# rings_v30.net
KiCad netlist of a schematic drawn in EAGLE
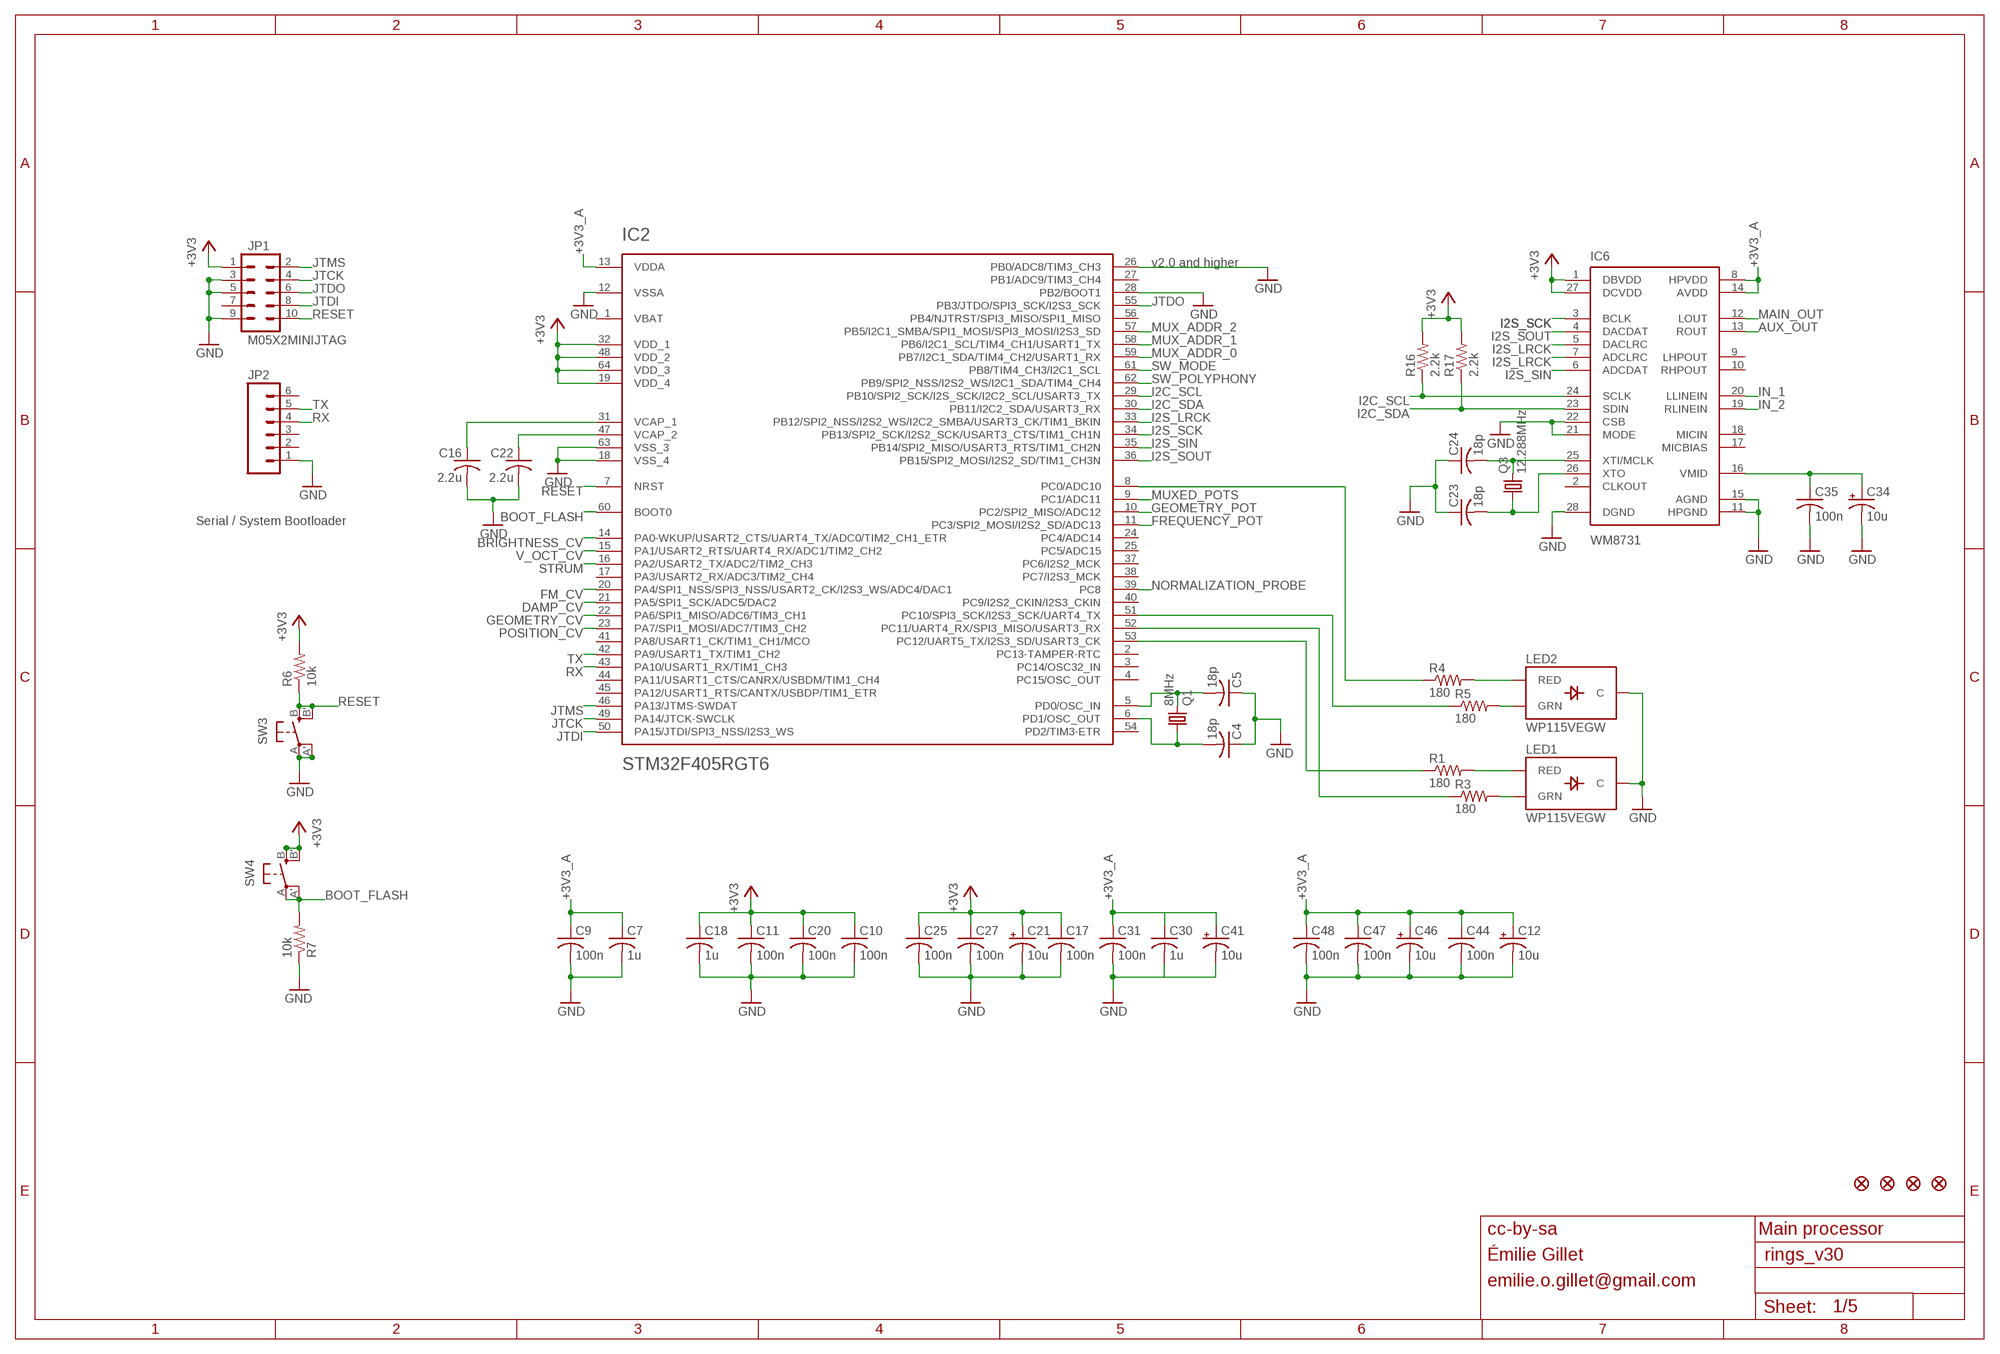
[diagram p0: schematic, sheet 1]
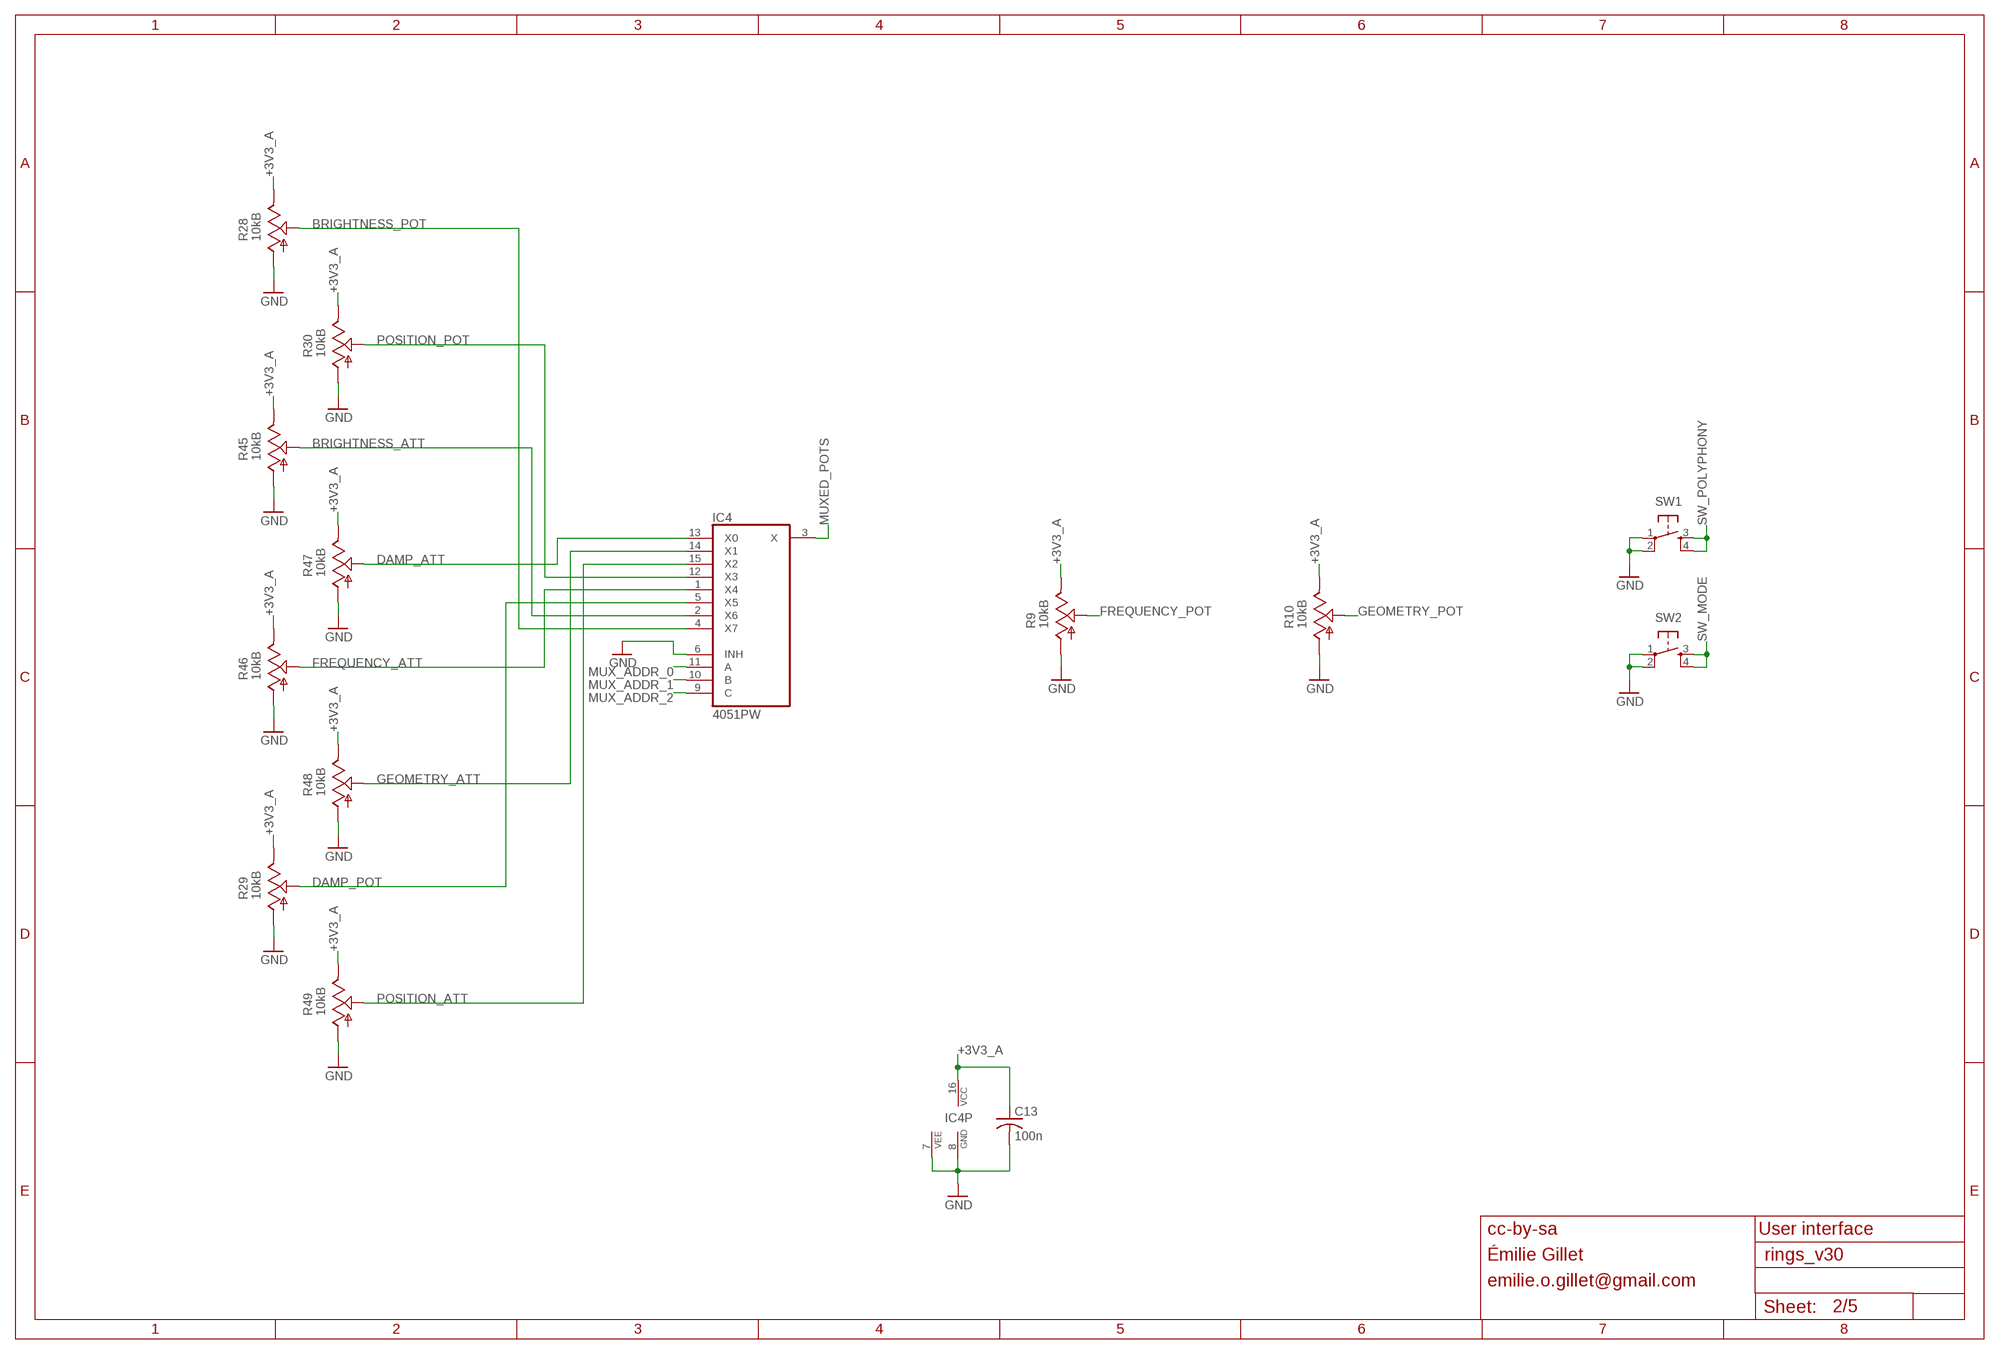
[diagram p1: schematic, sheet 2]
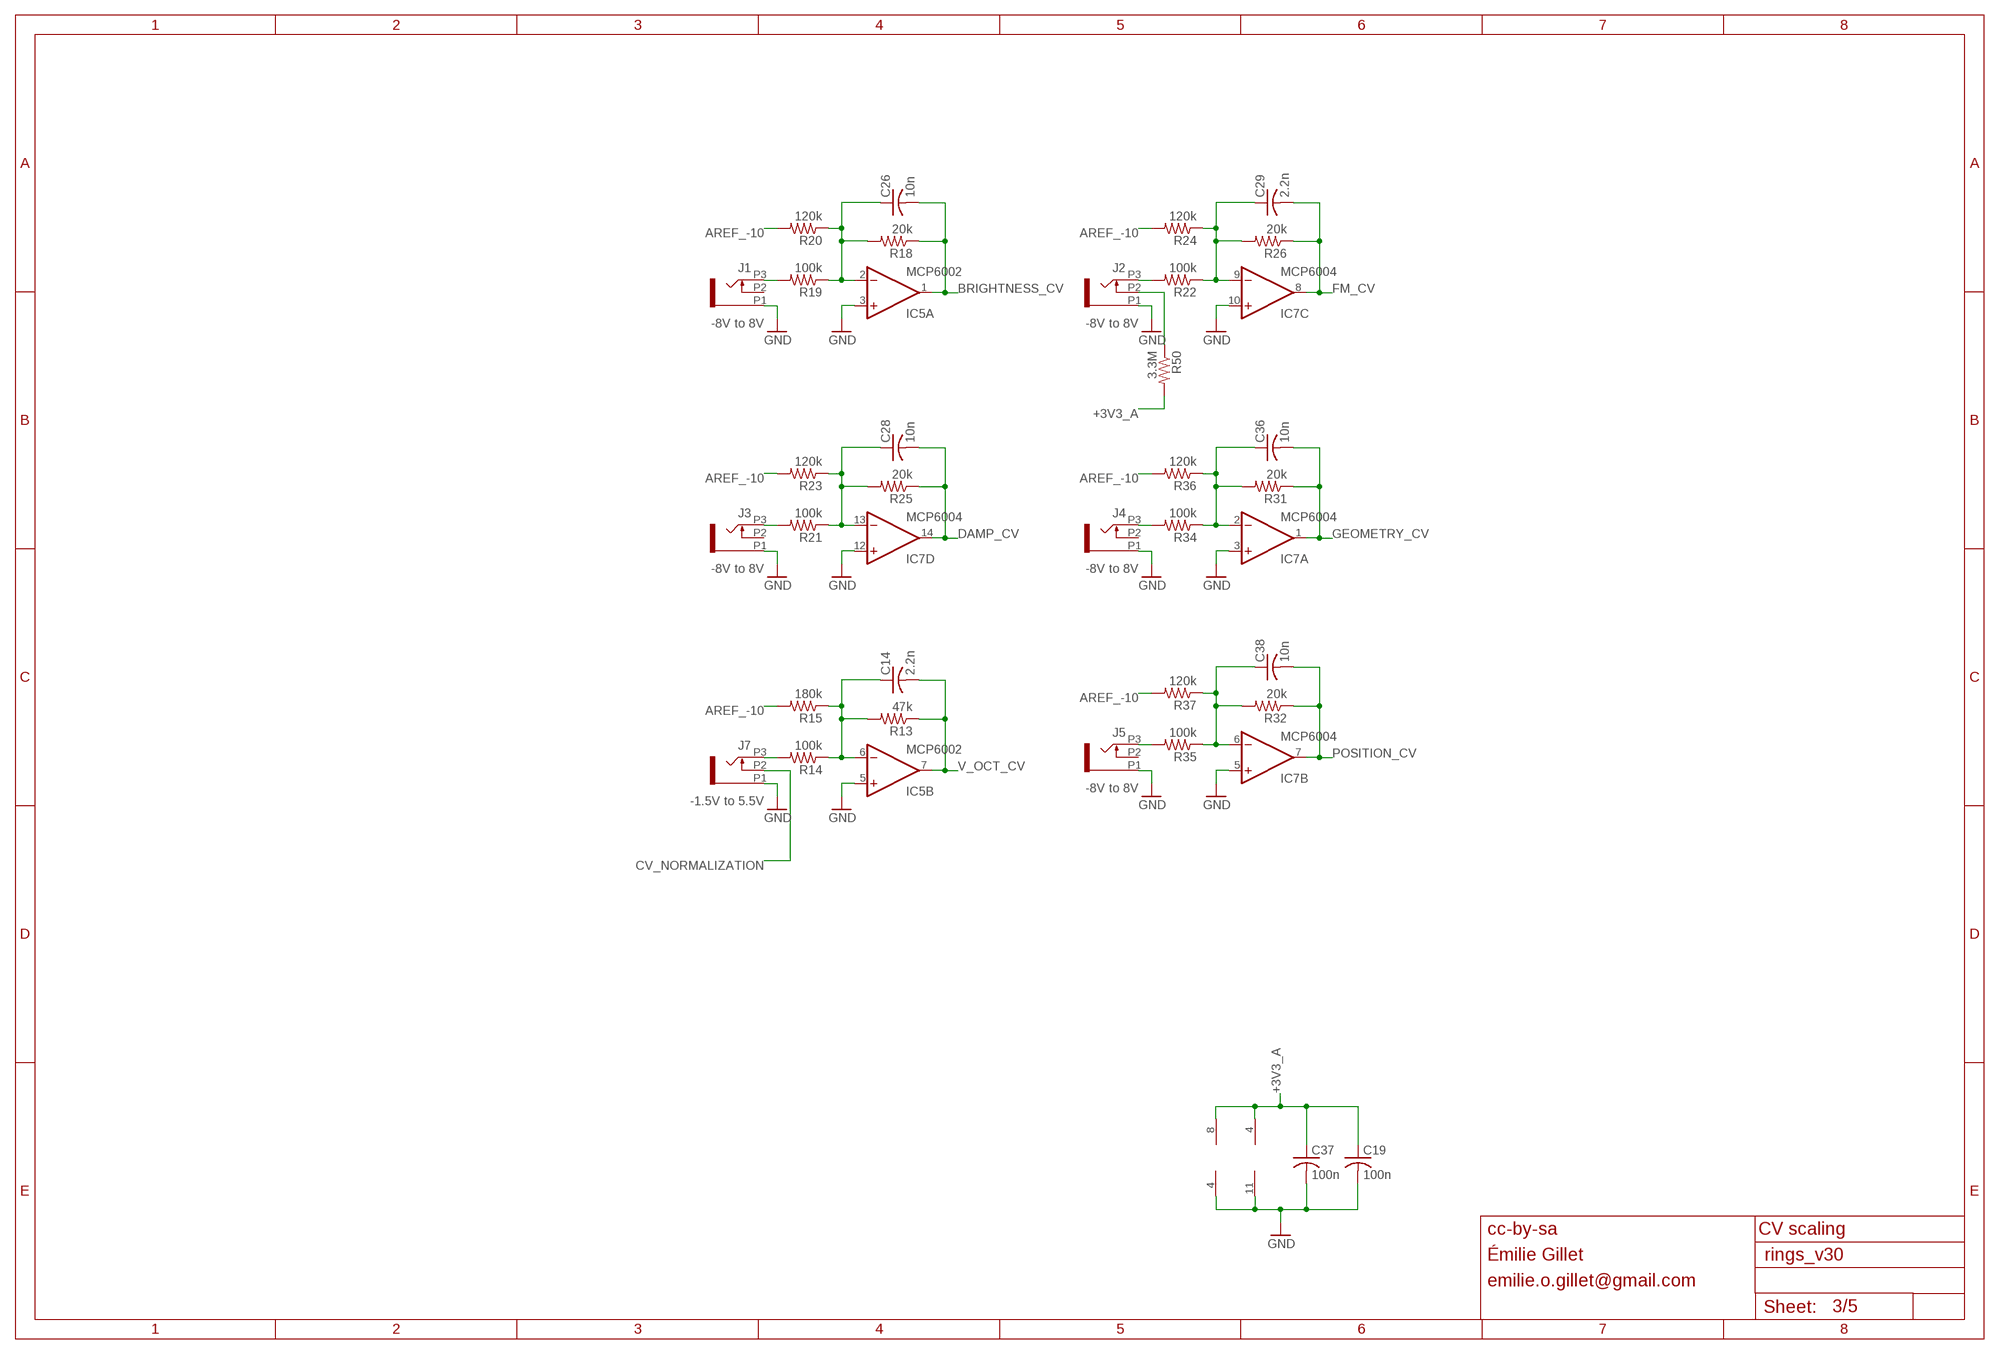
[diagram p2: schematic, sheet 3]
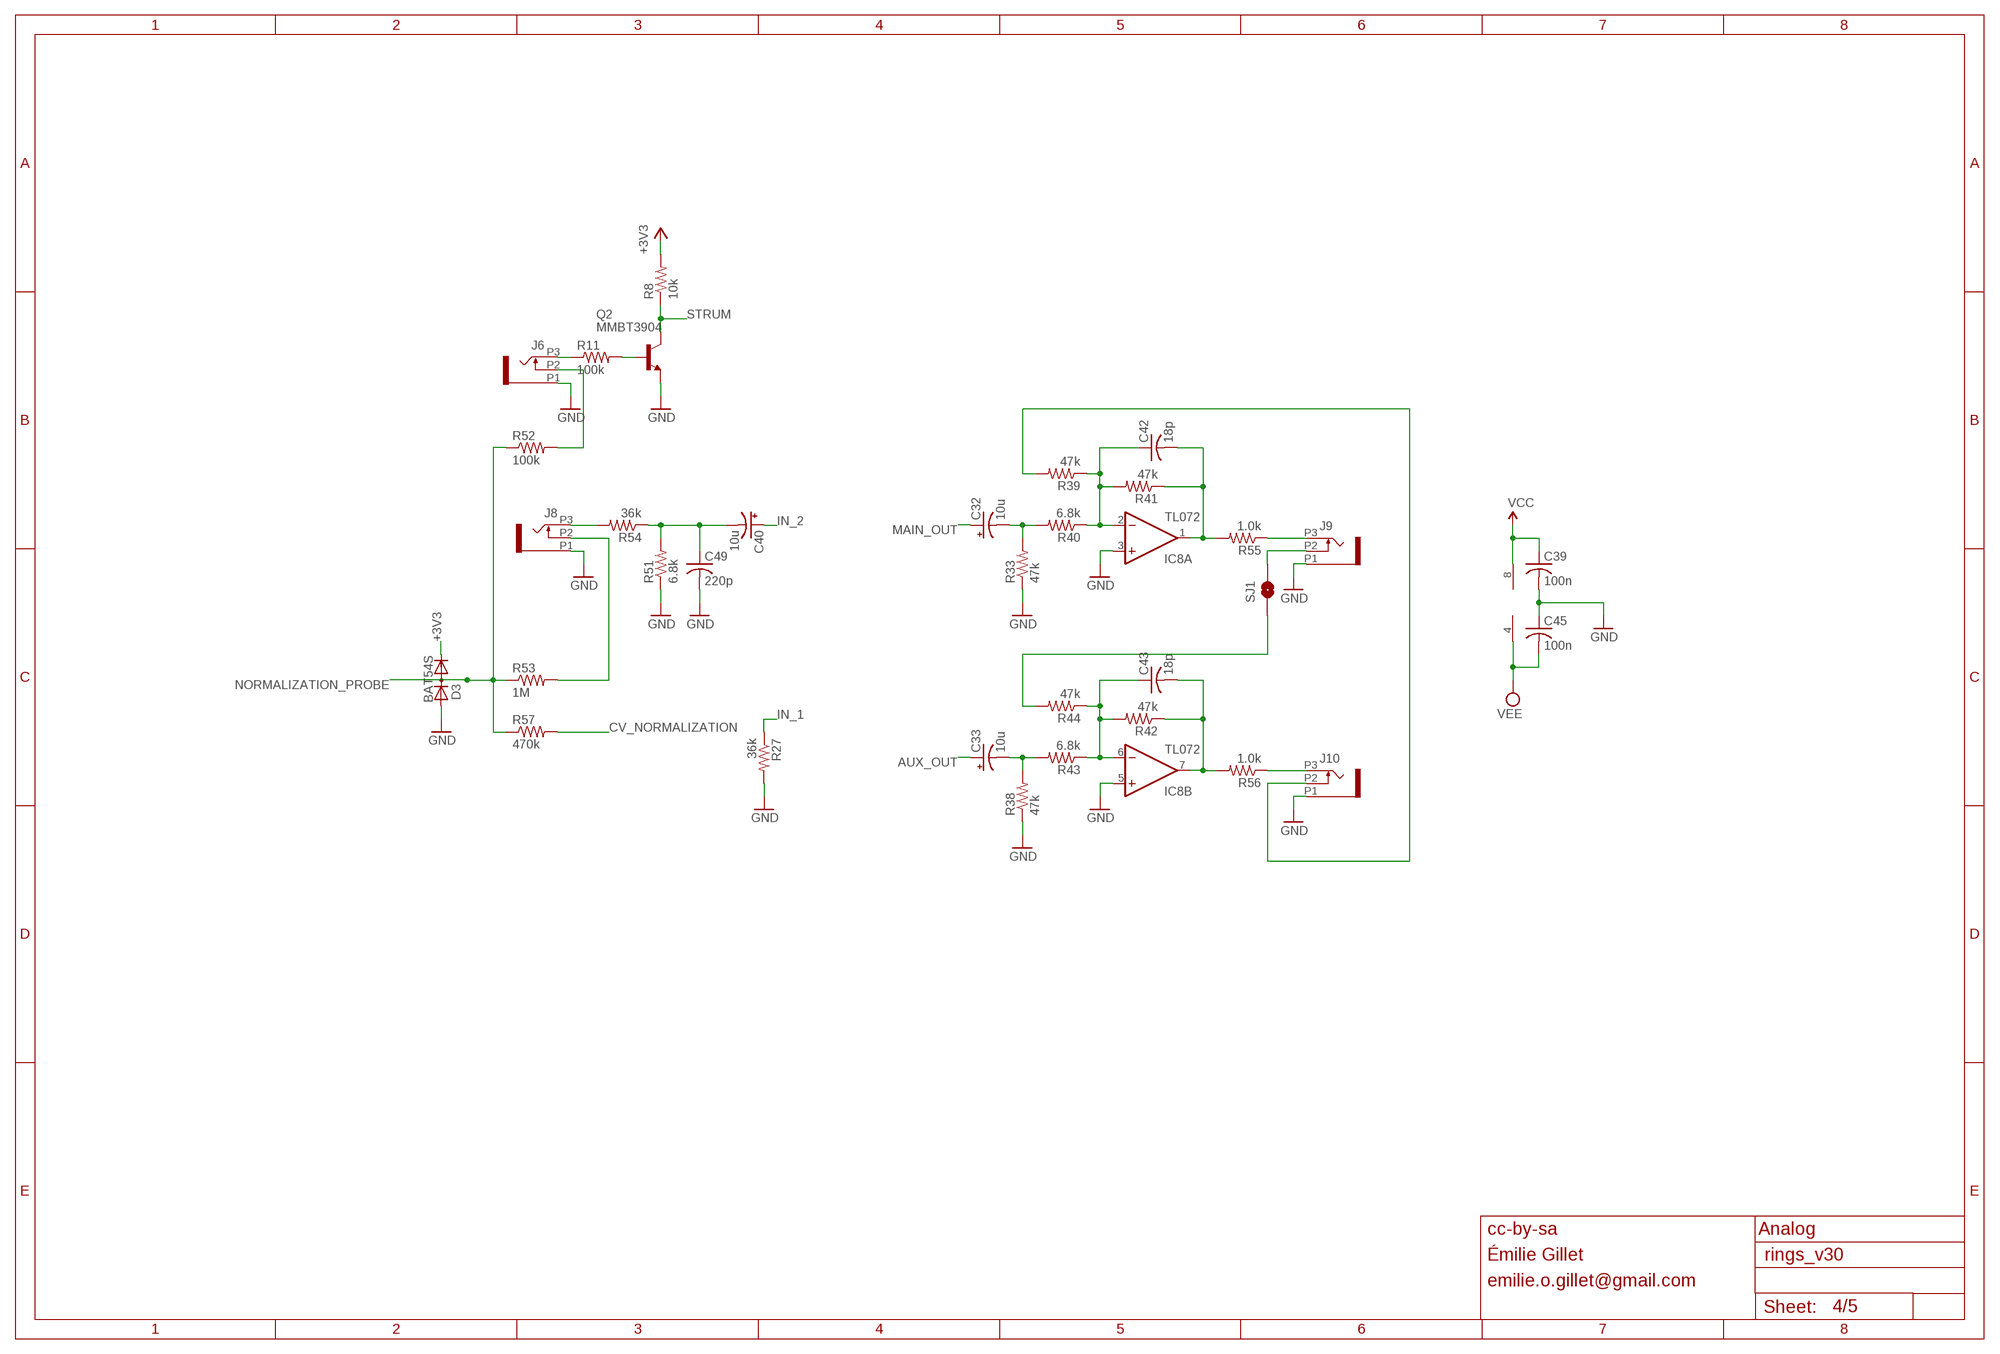
[diagram p3: schematic, sheet 4]
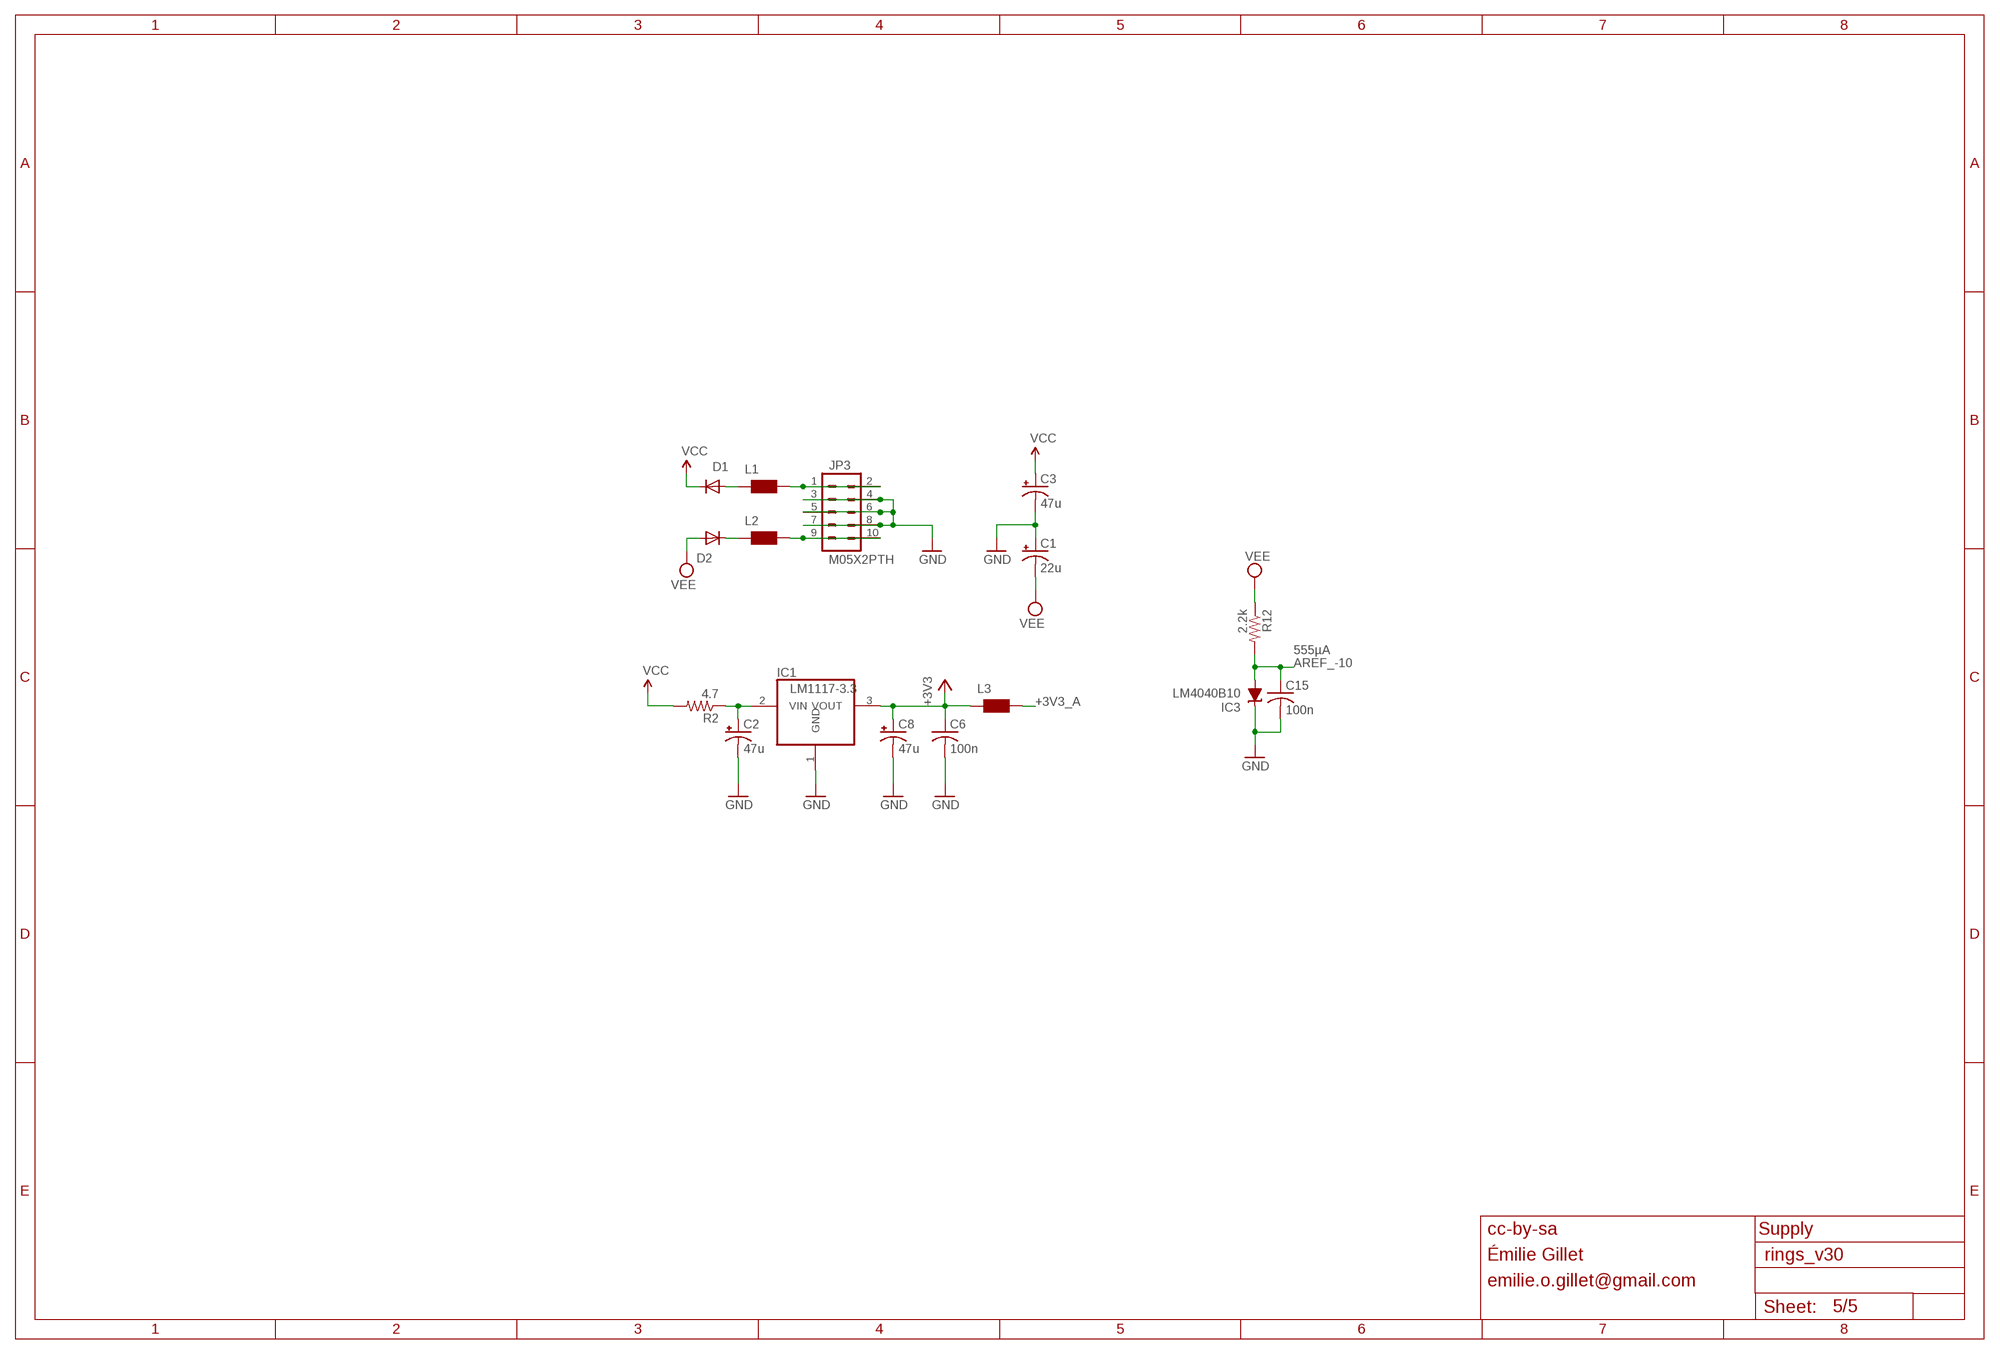
[diagram p4: schematic, sheet 5]

(export (version "E")
  (design (tool "Eeschema 10.0.6"))
  (components
    (comp (ref "C32")
      (value "10u")
      (footprint "eagle-import:PANASONIC_A")
      (libsource (lib "eagle-import") (part "CPOL-USA"))
    )
    (comp (ref "C33")
      (value "10u")
      (footprint "eagle-import:PANASONIC_A")
      (libsource (lib "eagle-import") (part "CPOL-USA"))
    )
    (comp (ref "C39")
      (value "100n")
      (footprint "eagle-import:C0603")
      (libsource (lib "eagle-import") (part "C-USC0603"))
    )
    (comp (ref "C40")
      (value "10u")
      (footprint "eagle-import:PANASONIC_A")
      (libsource (lib "eagle-import") (part "CPOL-USA"))
    )
    (comp (ref "C42")
      (value "18p")
      (footprint "eagle-import:C0603")
      (libsource (lib "eagle-import") (part "C-USC0603"))
    )
    (comp (ref "C43")
      (value "18p")
      (footprint "eagle-import:C0603")
      (libsource (lib "eagle-import") (part "C-USC0603"))
    )
    (comp (ref "C45")
      (value "100n")
      (footprint "eagle-import:C0603")
      (libsource (lib "eagle-import") (part "C-USC0603"))
    )
    (comp (ref "C49")
      (value "220p")
      (footprint "eagle-import:C0603")
      (libsource (lib "eagle-import") (part "C-USC0603"))
    )
    (comp (ref "D3")
      (value "BAT54S")
      (footprint "eagle-import:SOT23")
      (libsource (lib "eagle-import") (part "DIODE_2CACA-SOT23"))
    )
    (comp (ref "IC8")
      (value "TL072")
      (footprint "eagle-import:SO08")
      (libsource (lib "eagle-import") (part "og-linear_TL072D"))
    )
    (comp (ref "J6")
      (value "PJ301_THONKICONN6")
      (footprint "eagle-import:WQP_PJ_301M6")
      (libsource (lib "eagle-import") (part "PJ301_THONKICONN6"))
    )
    (comp (ref "J8")
      (value "PJ301_THONKICONN6")
      (footprint "eagle-import:WQP_PJ_301M6")
      (libsource (lib "eagle-import") (part "PJ301_THONKICONN6"))
    )
    (comp (ref "J9")
      (value "PJ301_THONKICONN6")
      (footprint "eagle-import:WQP_PJ_301M6")
      (libsource (lib "eagle-import") (part "PJ301_THONKICONN6"))
    )
    (comp (ref "J10")
      (value "PJ301_THONKICONN6")
      (footprint "eagle-import:WQP_PJ_301M6")
      (libsource (lib "eagle-import") (part "PJ301_THONKICONN6"))
    )
    (comp (ref "Q2")
      (value "MMBT3904")
      (footprint "eagle-import:SOT23-BEC")
      (libsource (lib "eagle-import") (part "-NPN-SOT23-BECMMBT3904LT1"))
    )
    (comp (ref "R8")
      (value "10k")
      (footprint "eagle-import:R0603")
      (libsource (lib "eagle-import") (part "R-US_R0603"))
    )
    (comp (ref "R11")
      (value "100k")
      (footprint "eagle-import:R0603")
      (libsource (lib "eagle-import") (part "R-US_R0603"))
    )
    (comp (ref "R27")
      (value "36k")
      (footprint "eagle-import:R0603")
      (libsource (lib "eagle-import") (part "R-US_R0603"))
    )
    (comp (ref "R33")
      (value "47k")
      (footprint "eagle-import:R0603")
      (libsource (lib "eagle-import") (part "R-US_R0603"))
    )
    (comp (ref "R38")
      (value "47k")
      (footprint "eagle-import:R0603")
      (libsource (lib "eagle-import") (part "R-US_R0603"))
    )
    (comp (ref "R39")
      (value "47k")
      (footprint "eagle-import:R0603")
      (libsource (lib "eagle-import") (part "R-US_R0603"))
    )
    (comp (ref "R40")
      (value "6.8k")
      (footprint "eagle-import:R0603")
      (libsource (lib "eagle-import") (part "R-US_R0603"))
    )
    (comp (ref "R41")
      (value "47k")
      (footprint "eagle-import:R0603")
      (libsource (lib "eagle-import") (part "R-US_R0603"))
    )
    (comp (ref "R42")
      (value "47k")
      (footprint "eagle-import:R0603")
      (libsource (lib "eagle-import") (part "R-US_R0603"))
    )
    (comp (ref "R43")
      (value "6.8k")
      (footprint "eagle-import:R0603")
      (libsource (lib "eagle-import") (part "R-US_R0603"))
    )
    (comp (ref "R44")
      (value "47k")
      (footprint "eagle-import:R0603")
      (libsource (lib "eagle-import") (part "R-US_R0603"))
    )
    (comp (ref "R51")
      (value "6.8k")
      (footprint "eagle-import:R0603")
      (libsource (lib "eagle-import") (part "R-US_R0603"))
    )
    (comp (ref "R52")
      (value "100k")
      (footprint "eagle-import:R0603")
      (libsource (lib "eagle-import") (part "R-US_R0603"))
    )
    (comp (ref "R53")
      (value "1M")
      (footprint "eagle-import:R0603")
      (libsource (lib "eagle-import") (part "R-US_R0603"))
    )
    (comp (ref "R54")
      (value "36k")
      (footprint "eagle-import:R0603")
      (libsource (lib "eagle-import") (part "R-US_R0603"))
    )
    (comp (ref "R55")
      (value "1.0k")
      (footprint "eagle-import:R0603")
      (libsource (lib "eagle-import") (part "R-US_R0603"))
    )
    (comp (ref "R56")
      (value "1.0k")
      (footprint "eagle-import:R0603")
      (libsource (lib "eagle-import") (part "R-US_R0603"))
    )
    (comp (ref "R57")
      (value "470k")
      (footprint "eagle-import:R0603")
      (libsource (lib "eagle-import") (part "R-US_R0603"))
    )
    (comp (ref "SJ1")
      (value "SOLDERJUMPERNC2")
      (footprint "eagle-import:SJ_2S-NOTRACE")
      (libsource (lib "eagle-import") (part "SOLDERJUMPERNC2"))
    )
    (comp (ref "C4")
      (value "18p")
      (footprint "eagle-import:C0603")
      (libsource (lib "eagle-import") (part "C-USC0603"))
    )
    (comp (ref "C5")
      (value "18p")
      (footprint "eagle-import:C0603")
      (libsource (lib "eagle-import") (part "C-USC0603"))
    )
    (comp (ref "C7")
      (value "1u")
      (footprint "eagle-import:C0603")
      (libsource (lib "eagle-import") (part "C-USC0603"))
    )
    (comp (ref "C9")
      (value "100n")
      (footprint "eagle-import:C0603")
      (libsource (lib "eagle-import") (part "C-USC0603"))
    )
    (comp (ref "C10")
      (value "100n")
      (footprint "eagle-import:C0603")
      (libsource (lib "eagle-import") (part "C-USC0603"))
    )
    (comp (ref "C11")
      (value "100n")
      (footprint "eagle-import:C0603")
      (libsource (lib "eagle-import") (part "C-USC0603"))
    )
    (comp (ref "C12")
      (value "10u")
      (footprint "eagle-import:PANASONIC_A")
      (libsource (lib "eagle-import") (part "CPOL-USA"))
    )
    (comp (ref "C16")
      (value "2.2u")
      (footprint "eagle-import:C0805")
      (libsource (lib "eagle-import") (part "C-USC0805"))
    )
    (comp (ref "C17")
      (value "100n")
      (footprint "eagle-import:C0603")
      (libsource (lib "eagle-import") (part "C-USC0603"))
    )
    (comp (ref "C18")
      (value "1u")
      (footprint "eagle-import:C0603")
      (libsource (lib "eagle-import") (part "C-USC0603"))
    )
    (comp (ref "C20")
      (value "100n")
      (footprint "eagle-import:C0603")
      (libsource (lib "eagle-import") (part "C-USC0603"))
    )
    (comp (ref "C21")
      (value "10u")
      (footprint "eagle-import:PANASONIC_A")
      (libsource (lib "eagle-import") (part "CPOL-USA"))
    )
    (comp (ref "C22")
      (value "2.2u")
      (footprint "eagle-import:C0805")
      (libsource (lib "eagle-import") (part "C-USC0805"))
    )
    (comp (ref "C23")
      (value "18p")
      (footprint "eagle-import:C0603")
      (libsource (lib "eagle-import") (part "C-USC0603"))
    )
    (comp (ref "C24")
      (value "18p")
      (footprint "eagle-import:C0603")
      (libsource (lib "eagle-import") (part "C-USC0603"))
    )
    (comp (ref "C25")
      (value "100n")
      (footprint "eagle-import:C0603")
      (libsource (lib "eagle-import") (part "C-USC0603"))
    )
    (comp (ref "C27")
      (value "100n")
      (footprint "eagle-import:C0603")
      (libsource (lib "eagle-import") (part "C-USC0603"))
    )
    (comp (ref "C30")
      (value "1u")
      (footprint "eagle-import:C0603")
      (libsource (lib "eagle-import") (part "C-USC0603"))
    )
    (comp (ref "C31")
      (value "100n")
      (footprint "eagle-import:C0603")
      (libsource (lib "eagle-import") (part "C-USC0603"))
    )
    (comp (ref "C34")
      (value "10u")
      (footprint "eagle-import:PANASONIC_A")
      (libsource (lib "eagle-import") (part "CPOL-USA"))
    )
    (comp (ref "C35")
      (value "100n")
      (footprint "eagle-import:C0603")
      (libsource (lib "eagle-import") (part "C-USC0603"))
    )
    (comp (ref "C41")
      (value "10u")
      (footprint "eagle-import:PANASONIC_A")
      (libsource (lib "eagle-import") (part "CPOL-USA"))
    )
    (comp (ref "C44")
      (value "100n")
      (footprint "eagle-import:C0603")
      (libsource (lib "eagle-import") (part "C-USC0603"))
    )
    (comp (ref "C46")
      (value "10u")
      (footprint "eagle-import:PANASONIC_A")
      (libsource (lib "eagle-import") (part "CPOL-USA"))
    )
    (comp (ref "C47")
      (value "100n")
      (footprint "eagle-import:C0603")
      (libsource (lib "eagle-import") (part "C-USC0603"))
    )
    (comp (ref "C48")
      (value "100n")
      (footprint "eagle-import:C0603")
      (libsource (lib "eagle-import") (part "C-USC0603"))
    )
    (comp (ref "F1")
      (value "FIDUCIAL1X2")
      (footprint "eagle-import:FIDUCIAL-1X2")
      (libsource (lib "eagle-import") (part "FIDUCIAL1X2"))
    )
    (comp (ref "F2")
      (value "FIDUCIAL1X2")
      (footprint "eagle-import:FIDUCIAL-1X2")
      (libsource (lib "eagle-import") (part "FIDUCIAL1X2"))
    )
    (comp (ref "F3")
      (value "FIDUCIAL1X2")
      (footprint "eagle-import:FIDUCIAL-1X2")
      (libsource (lib "eagle-import") (part "FIDUCIAL1X2"))
    )
    (comp (ref "F4")
      (value "FIDUCIAL1X2")
      (footprint "eagle-import:FIDUCIAL-1X2")
      (libsource (lib "eagle-import") (part "FIDUCIAL1X2"))
    )
    (comp (ref "IC2")
      (value "STM32F405RGT6")
      (footprint "eagle-import:TQFP-10X10-64")
      (libsource (lib "eagle-import") (part "STM32F20X"))
    )
    (comp (ref "IC6")
      (value "WM8731")
      (footprint "eagle-import:SSOP28")
      (libsource (lib "eagle-import") (part "WM8731"))
    )
    (comp (ref "JP1")
      (value "M05X2MINIJTAG")
      (footprint "eagle-import:2X5-1.27")
      (libsource (lib "eagle-import") (part "M05X2MINIJTAG"))
    )
    (comp (ref "JP2")
      (value "M06SIP")
      (footprint "eagle-import:1X06")
      (libsource (lib "eagle-import") (part "M06SIP"))
    )
    (comp (ref "LED1")
      (value "WP115VEGW")
      (footprint "eagle-import:LED-BICOLOR-THROUGHHOLE")
      (libsource (lib "eagle-import") (part "LED-BICOLOR-THROUGHHOLE"))
    )
    (comp (ref "LED2")
      (value "WP115VEGW")
      (footprint "eagle-import:LED-BICOLOR-THROUGHHOLE")
      (libsource (lib "eagle-import") (part "LED-BICOLOR-THROUGHHOLE"))
    )
    (comp (ref "Q1")
      (value "8MHz")
      (footprint "eagle-import:HC49UP")
      (libsource (lib "eagle-import") (part "CRYSTALHC49UP"))
    )
    (comp (ref "Q3")
      (value "12.288MHz")
      (footprint "eagle-import:HC49UP")
      (libsource (lib "eagle-import") (part "CRYSTALHC49UP"))
    )
    (comp (ref "R1")
      (value "180")
      (footprint "eagle-import:R0603")
      (libsource (lib "eagle-import") (part "R-US_R0603"))
    )
    (comp (ref "R3")
      (value "180")
      (footprint "eagle-import:R0603")
      (libsource (lib "eagle-import") (part "R-US_R0603"))
    )
    (comp (ref "R4")
      (value "180")
      (footprint "eagle-import:R0603")
      (libsource (lib "eagle-import") (part "R-US_R0603"))
    )
    (comp (ref "R5")
      (value "180")
      (footprint "eagle-import:R0603")
      (libsource (lib "eagle-import") (part "R-US_R0603"))
    )
    (comp (ref "R6")
      (value "10k")
      (footprint "eagle-import:R0603")
      (libsource (lib "eagle-import") (part "R-US_R0603"))
    )
    (comp (ref "R7")
      (value "10k")
      (footprint "eagle-import:R0603")
      (libsource (lib "eagle-import") (part "R-US_R0603"))
    )
    (comp (ref "R16")
      (value "2.2k")
      (footprint "eagle-import:R0603")
      (libsource (lib "eagle-import") (part "R-US_R0603"))
    )
    (comp (ref "R17")
      (value "2.2k")
      (footprint "eagle-import:R0603")
      (libsource (lib "eagle-import") (part "R-US_R0603"))
    )
    (comp (ref "SW3")
      (value "EVQQ2")
      (footprint "eagle-import:EVQ-Q2")
      (libsource (lib "eagle-import") (part "EVQQ2"))
    )
    (comp (ref "SW4")
      (value "EVQQ2")
      (footprint "eagle-import:EVQ-Q2")
      (libsource (lib "eagle-import") (part "EVQQ2"))
    )
    (comp (ref "C14")
      (value "2.2n")
      (footprint "eagle-import:C0603")
      (libsource (lib "eagle-import") (part "C-USC0603"))
    )
    (comp (ref "C19")
      (value "100n")
      (footprint "eagle-import:C0603")
      (libsource (lib "eagle-import") (part "C-USC0603"))
    )
    (comp (ref "C26")
      (value "10n")
      (footprint "eagle-import:C0603")
      (libsource (lib "eagle-import") (part "C-USC0603"))
    )
    (comp (ref "C28")
      (value "10n")
      (footprint "eagle-import:C0603")
      (libsource (lib "eagle-import") (part "C-USC0603"))
    )
    (comp (ref "C29")
      (value "2.2n")
      (footprint "eagle-import:C0603")
      (libsource (lib "eagle-import") (part "C-USC0603"))
    )
    (comp (ref "C36")
      (value "10n")
      (footprint "eagle-import:C0603")
      (libsource (lib "eagle-import") (part "C-USC0603"))
    )
    (comp (ref "C37")
      (value "100n")
      (footprint "eagle-import:C0603")
      (libsource (lib "eagle-import") (part "C-USC0603"))
    )
    (comp (ref "C38")
      (value "10n")
      (footprint "eagle-import:C0603")
      (libsource (lib "eagle-import") (part "C-USC0603"))
    )
    (comp (ref "IC5")
      (value "MCP6002")
      (footprint "eagle-import:SO08")
      (libsource (lib "eagle-import") (part "TL072D"))
    )
    (comp (ref "IC7")
      (value "MCP6004")
      (footprint "eagle-import:SO14")
      (libsource (lib "eagle-import") (part "TL074D"))
    )
    (comp (ref "J1")
      (value "PJ301_THONKICONN6")
      (footprint "eagle-import:WQP_PJ_301M6")
      (libsource (lib "eagle-import") (part "PJ301_THONKICONN6"))
    )
    (comp (ref "J2")
      (value "PJ301_THONKICONN6")
      (footprint "eagle-import:WQP_PJ_301M6")
      (libsource (lib "eagle-import") (part "PJ301_THONKICONN6"))
    )
    (comp (ref "J3")
      (value "PJ301_THONKICONN6")
      (footprint "eagle-import:WQP_PJ_301M6")
      (libsource (lib "eagle-import") (part "PJ301_THONKICONN6"))
    )
    (comp (ref "J4")
      (value "PJ301_THONKICONN6")
      (footprint "eagle-import:WQP_PJ_301M6")
      (libsource (lib "eagle-import") (part "PJ301_THONKICONN6"))
    )
    (comp (ref "J5")
      (value "PJ301_THONKICONN6")
      (footprint "eagle-import:WQP_PJ_301M6")
      (libsource (lib "eagle-import") (part "PJ301_THONKICONN6"))
    )
    (comp (ref "J7")
      (value "PJ301_THONKICONN6")
      (footprint "eagle-import:WQP_PJ_301M6")
      (libsource (lib "eagle-import") (part "PJ301_THONKICONN6"))
    )
    (comp (ref "R13")
      (value "47k")
      (footprint "eagle-import:R0603")
      (libsource (lib "eagle-import") (part "R-US_R0603"))
    )
    (comp (ref "R14")
      (value "100k")
      (footprint "eagle-import:R0603")
      (libsource (lib "eagle-import") (part "R-US_R0603"))
    )
    (comp (ref "R15")
      (value "180k")
      (footprint "eagle-import:R0603")
      (libsource (lib "eagle-import") (part "R-US_R0603"))
    )
    (comp (ref "R18")
      (value "20k")
      (footprint "eagle-import:R0603")
      (libsource (lib "eagle-import") (part "R-US_R0603"))
    )
    (comp (ref "R19")
      (value "100k")
      (footprint "eagle-import:R0603")
      (libsource (lib "eagle-import") (part "R-US_R0603"))
    )
    (comp (ref "R20")
      (value "120k")
      (footprint "eagle-import:R0603")
      (libsource (lib "eagle-import") (part "R-US_R0603"))
    )
    (comp (ref "R21")
      (value "100k")
      (footprint "eagle-import:R0603")
      (libsource (lib "eagle-import") (part "R-US_R0603"))
    )
    (comp (ref "R22")
      (value "100k")
      (footprint "eagle-import:R0603")
      (libsource (lib "eagle-import") (part "R-US_R0603"))
    )
    (comp (ref "R23")
      (value "120k")
      (footprint "eagle-import:R0603")
      (libsource (lib "eagle-import") (part "R-US_R0603"))
    )
    (comp (ref "R24")
      (value "120k")
      (footprint "eagle-import:R0603")
      (libsource (lib "eagle-import") (part "R-US_R0603"))
    )
    (comp (ref "R25")
      (value "20k")
      (footprint "eagle-import:R0603")
      (libsource (lib "eagle-import") (part "R-US_R0603"))
    )
    (comp (ref "R26")
      (value "20k")
      (footprint "eagle-import:R0603")
      (libsource (lib "eagle-import") (part "R-US_R0603"))
    )
    (comp (ref "R31")
      (value "20k")
      (footprint "eagle-import:R0603")
      (libsource (lib "eagle-import") (part "R-US_R0603"))
    )
    (comp (ref "R32")
      (value "20k")
      (footprint "eagle-import:R0603")
      (libsource (lib "eagle-import") (part "R-US_R0603"))
    )
    (comp (ref "R34")
      (value "100k")
      (footprint "eagle-import:R0603")
      (libsource (lib "eagle-import") (part "R-US_R0603"))
    )
    (comp (ref "R35")
      (value "100k")
      (footprint "eagle-import:R0603")
      (libsource (lib "eagle-import") (part "R-US_R0603"))
    )
    (comp (ref "R36")
      (value "120k")
      (footprint "eagle-import:R0603")
      (libsource (lib "eagle-import") (part "R-US_R0603"))
    )
    (comp (ref "R37")
      (value "120k")
      (footprint "eagle-import:R0603")
      (libsource (lib "eagle-import") (part "R-US_R0603"))
    )
    (comp (ref "R50")
      (value "3.3M")
      (footprint "eagle-import:R0603")
      (libsource (lib "eagle-import") (part "R-US_R0603"))
    )
    (comp (ref "C13")
      (value "100n")
      (footprint "eagle-import:C0603")
      (libsource (lib "eagle-import") (part "C-USC0603"))
    )
    (comp (ref "IC4")
      (value "4051PW")
      (footprint "eagle-import:TSSOP16")
      (libsource (lib "eagle-import") (part "4051PW"))
    )
    (comp (ref "R9")
      (value "10kB")
      (footprint "eagle-import:ALPS_POT_VERTICAL_PS")
      (libsource (lib "eagle-import") (part "POT_USVERTICAL_PS"))
    )
    (comp (ref "R10")
      (value "10kB")
      (footprint "eagle-import:ALPS_POT_VERTICAL_PS")
      (libsource (lib "eagle-import") (part "POT_USVERTICAL_PS"))
    )
    (comp (ref "R28")
      (value "10kB")
      (footprint "eagle-import:ALPS_POT_VERTICAL_PS")
      (libsource (lib "eagle-import") (part "POT_USVERTICAL_PS"))
    )
    (comp (ref "R29")
      (value "10kB")
      (footprint "eagle-import:ALPS_POT_VERTICAL_PS")
      (libsource (lib "eagle-import") (part "POT_USVERTICAL_PS"))
    )
    (comp (ref "R30")
      (value "10kB")
      (footprint "eagle-import:ALPS_POT_VERTICAL_PS")
      (libsource (lib "eagle-import") (part "POT_USVERTICAL_PS"))
    )
    (comp (ref "R45")
      (value "10kB")
      (footprint "eagle-import:ALPS_POT_VERTICAL")
      (libsource (lib "eagle-import") (part "POT_USVERTICAL"))
    )
    (comp (ref "R46")
      (value "10kB")
      (footprint "eagle-import:ALPS_POT_VERTICAL")
      (libsource (lib "eagle-import") (part "POT_USVERTICAL"))
    )
    (comp (ref "R47")
      (value "10kB")
      (footprint "eagle-import:ALPS_POT_VERTICAL")
      (libsource (lib "eagle-import") (part "POT_USVERTICAL"))
    )
    (comp (ref "R48")
      (value "10kB")
      (footprint "eagle-import:ALPS_POT_VERTICAL")
      (libsource (lib "eagle-import") (part "POT_USVERTICAL"))
    )
    (comp (ref "R49")
      (value "10kB")
      (footprint "eagle-import:ALPS_POT_VERTICAL")
      (libsource (lib "eagle-import") (part "POT_USVERTICAL"))
    )
    (comp (ref "SW1")
      (value "TAC_SWITCHPTH")
      (footprint "eagle-import:TACTILE-PTH")
      (libsource (lib "eagle-import") (part "TAC_SWITCHPTH"))
    )
    (comp (ref "SW2")
      (value "TAC_SWITCHPTH")
      (footprint "eagle-import:TACTILE-PTH")
      (libsource (lib "eagle-import") (part "TAC_SWITCHPTH"))
    )
    (comp (ref "C1")
      (value "22u")
      (footprint "eagle-import:PANASONIC_C")
      (libsource (lib "eagle-import") (part "CPOL-USC"))
    )
    (comp (ref "C2")
      (value "47u")
      (footprint "eagle-import:PANASONIC_D")
      (libsource (lib "eagle-import") (part "CPOL-USD"))
    )
    (comp (ref "C3")
      (value "47u")
      (footprint "eagle-import:PANASONIC_D")
      (libsource (lib "eagle-import") (part "CPOL-USD"))
    )
    (comp (ref "C6")
      (value "100n")
      (footprint "eagle-import:C0603")
      (libsource (lib "eagle-import") (part "C-USC0603"))
    )
    (comp (ref "C8")
      (value "47u")
      (footprint "eagle-import:PANASONIC_D")
      (libsource (lib "eagle-import") (part "CPOL-USD"))
    )
    (comp (ref "C15")
      (value "100n")
      (footprint "eagle-import:C0603")
      (libsource (lib "eagle-import") (part "C-USC0603"))
    )
    (comp (ref "D1")
      (value "1N5819HW")
      (footprint "eagle-import:SOD123")
      (libsource (lib "eagle-import") (part "DIODE-SOD123"))
    )
    (comp (ref "D2")
      (value "1N5819HW")
      (footprint "eagle-import:SOD123")
      (libsource (lib "eagle-import") (part "DIODE-SOD123"))
    )
    (comp (ref "IC1")
      (value "LM1117-3.3")
      (footprint "eagle-import:TO252")
      (libsource (lib "eagle-import") (part "REG1117T"))
    )
    (comp (ref "IC3")
      (value "LM4040B10")
      (footprint "eagle-import:DBZ_R-PDSO-G3")
      (libsource (lib "eagle-import") (part "LM4041DBZB12"))
    )
    (comp (ref "JP3")
      (value "M05X2PTH")
      (footprint "eagle-import:AVR_ICSP")
      (libsource (lib "eagle-import") (part "M05X2PTH"))
    )
    (comp (ref "L1")
      (value "WE-CBF_0603")
      (footprint "eagle-import:0603")
      (libsource (lib "eagle-import") (part "WE-CBF_0603"))
    )
    (comp (ref "L2")
      (value "WE-CBF_0603")
      (footprint "eagle-import:0603")
      (libsource (lib "eagle-import") (part "WE-CBF_0603"))
    )
    (comp (ref "L3")
      (value "WE-CBF_0603")
      (footprint "eagle-import:0603")
      (libsource (lib "eagle-import") (part "WE-CBF_0603"))
    )
    (comp (ref "R2")
      (value "4.7")
      (footprint "eagle-import:R1206")
      (libsource (lib "eagle-import") (part "R-US_R1206"))
    )
    (comp (ref "R12")
      (value "2.2k")
      (footprint "eagle-import:R0603")
      (libsource (lib "eagle-import") (part "R-US_R0603"))
    )
  )
  (nets
    (net (code "1") (name "+3V3") (class "Default")
      (node (ref "C10") (pin "1") (pinfunction "1_1") (pintype "passive"))
      (node (ref "C11") (pin "1") (pinfunction "1_1") (pintype "passive"))
      (node (ref "C17") (pin "1") (pinfunction "1_1") (pintype "passive"))
      (node (ref "C18") (pin "1") (pinfunction "1_1") (pintype "passive"))
      (node (ref "C20") (pin "1") (pinfunction "1_1") (pintype "passive"))
      (node (ref "C21") (pin "+") (pinfunction "+_+") (pintype "passive"))
      (node (ref "C25") (pin "1") (pinfunction "1_1") (pintype "passive"))
      (node (ref "C27") (pin "1") (pinfunction "1_1") (pintype "passive"))
      (node (ref "C6") (pin "1") (pinfunction "1_1") (pintype "passive"))
      (node (ref "C8") (pin "+") (pinfunction "+_+") (pintype "passive"))
      (node (ref "D3") (pin "2") (pinfunction "C_2") (pintype "passive"))
      (node (ref "IC1") (pin "3") (pinfunction "VOUT_3") (pintype "output"))
      (node (ref "IC2") (pin "19") (pinfunction "VDD_4_19") (pintype "power_in"))
      (node (ref "IC2") (pin "32") (pinfunction "VDD_1_32") (pintype "power_in"))
      (node (ref "IC2") (pin "48") (pinfunction "VDD_2_48") (pintype "power_in"))
      (node (ref "IC2") (pin "64") (pinfunction "VDD_3_64") (pintype "power_in"))
      (node (ref "IC6") (pin "1") (pinfunction "DBVDD_1") (pintype "bidirectional"))
      (node (ref "IC6") (pin "27") (pinfunction "DCVDD_27") (pintype "bidirectional"))
      (node (ref "JP1") (pin "1") (pinfunction "1_1") (pintype "passive"))
      (node (ref "L3") (pin "1") (pinfunction "1_1") (pintype "passive"))
      (node (ref "R16") (pin "2") (pinfunction "2_2") (pintype "passive"))
      (node (ref "R17") (pin "2") (pinfunction "2_2") (pintype "passive"))
      (node (ref "R6") (pin "2") (pinfunction "2_2") (pintype "passive"))
      (node (ref "R8") (pin "2") (pinfunction "2_2") (pintype "passive"))
      (node (ref "SW4") (pin "B") (pinfunction "S_B") (pintype "passive"))
      (node (ref "SW4") (pin "B'") (pinfunction "S1_B'") (pintype "passive"))
    )
    (net (code "2") (name "+3V3_A") (class "Default")
      (node (ref "C12") (pin "+") (pinfunction "+_+") (pintype "passive"))
      (node (ref "C13") (pin "1") (pinfunction "1_1") (pintype "passive"))
      (node (ref "C19") (pin "1") (pinfunction "1_1") (pintype "passive"))
      (node (ref "C30") (pin "1") (pinfunction "1_1") (pintype "passive"))
      (node (ref "C31") (pin "1") (pinfunction "1_1") (pintype "passive"))
      (node (ref "C37") (pin "1") (pinfunction "1_1") (pintype "passive"))
      (node (ref "C41") (pin "+") (pinfunction "+_+") (pintype "passive"))
      (node (ref "C44") (pin "1") (pinfunction "1_1") (pintype "passive"))
      (node (ref "C46") (pin "+") (pinfunction "+_+") (pintype "passive"))
      (node (ref "C47") (pin "1") (pinfunction "1_1") (pintype "passive"))
      (node (ref "C48") (pin "1") (pinfunction "1_1") (pintype "passive"))
      (node (ref "C7") (pin "1") (pinfunction "1_1") (pintype "passive"))
      (node (ref "C9") (pin "1") (pinfunction "1_1") (pintype "passive"))
      (node (ref "IC2") (pin "13") (pinfunction "VDDA_13") (pintype "power_in"))
      (node (ref "IC4") (pin "16") (pinfunction "VCC_16") (pintype "power_in"))
      (node (ref "IC5") (pin "8") (pinfunction "V+_8") (pintype "power_in"))
      (node (ref "IC6") (pin "14") (pinfunction "AVDD_14") (pintype "bidirectional"))
      (node (ref "IC6") (pin "8") (pinfunction "HPVDD_8") (pintype "bidirectional"))
      (node (ref "IC7") (pin "4") (pinfunction "V+_4") (pintype "power_in"))
      (node (ref "L3") (pin "2") (pinfunction "2_2") (pintype "passive"))
      (node (ref "R10") (pin "P$1") (pinfunction "E_P$1") (pintype "passive"))
      (node (ref "R28") (pin "P$1") (pinfunction "E_P$1") (pintype "passive"))
      (node (ref "R29") (pin "P$1") (pinfunction "E_P$1") (pintype "passive"))
      (node (ref "R30") (pin "P$1") (pinfunction "E_P$1") (pintype "passive"))
      (node (ref "R45") (pin "P$1") (pinfunction "E_P$1") (pintype "passive"))
      (node (ref "R46") (pin "P$1") (pinfunction "E_P$1") (pintype "passive"))
      (node (ref "R47") (pin "P$1") (pinfunction "E_P$1") (pintype "passive"))
      (node (ref "R48") (pin "P$1") (pinfunction "E_P$1") (pintype "passive"))
      (node (ref "R49") (pin "P$1") (pinfunction "E_P$1") (pintype "passive"))
      (node (ref "R50") (pin "2") (pinfunction "2_2") (pintype "passive"))
      (node (ref "R9") (pin "P$1") (pinfunction "E_P$1") (pintype "passive"))
    )
    (net (code "3") (name "AREF_-10") (class "Default")
      (node (ref "C15") (pin "1") (pinfunction "1_1") (pintype "passive"))
      (node (ref "IC3") (pin "2") (pinfunction "A_2") (pintype "passive"))
      (node (ref "R12") (pin "2") (pinfunction "2_2") (pintype "passive"))
      (node (ref "R15") (pin "2") (pinfunction "2_2") (pintype "passive"))
      (node (ref "R20") (pin "2") (pinfunction "2_2") (pintype "passive"))
      (node (ref "R23") (pin "2") (pinfunction "2_2") (pintype "passive"))
      (node (ref "R24") (pin "2") (pinfunction "2_2") (pintype "passive"))
      (node (ref "R36") (pin "2") (pinfunction "2_2") (pintype "passive"))
      (node (ref "R37") (pin "2") (pinfunction "2_2") (pintype "passive"))
    )
    (net (code "4") (name "AUX_OUT") (class "Default")
      (node (ref "C33") (pin "+") (pinfunction "+_+") (pintype "passive"))
      (node (ref "IC6") (pin "13") (pinfunction "ROUT_13") (pintype "bidirectional"))
    )
    (net (code "5") (name "BOOT_FLASH") (class "Default")
      (node (ref "IC2") (pin "60") (pinfunction "BOOT0_60") (pintype "bidirectional"))
      (node (ref "R7") (pin "2") (pinfunction "2_2") (pintype "passive"))
      (node (ref "SW4") (pin "A") (pinfunction "P_A") (pintype "passive"))
      (node (ref "SW4") (pin "A'") (pinfunction "P1_A'") (pintype "passive"))
    )
    (net (code "6") (name "BRIGHTNESS_ATT") (class "Default")
      (node (ref "IC4") (pin "2") (pinfunction "X6_2") (pintype "bidirectional"))
      (node (ref "R45") (pin "P$2") (pinfunction "S_P$2") (pintype "passive"))
    )
    (net (code "7") (name "BRIGHTNESS_CV") (class "Default")
      (node (ref "C26") (pin "2") (pinfunction "2_2") (pintype "passive"))
      (node (ref "IC2") (pin "14") (pinfunction "PA0-WKUP/USART2_CTS/UART4_TX/ADC0/TIM2_CH1_ETR_14") (pintype "bidirectional"))
      (node (ref "IC5") (pin "1") (pinfunction "OUT_1") (pintype "output"))
      (node (ref "R18") (pin "1") (pinfunction "1_1") (pintype "passive"))
    )
    (net (code "8") (name "BRIGHTNESS_POT") (class "Default")
      (node (ref "IC4") (pin "4") (pinfunction "X7_4") (pintype "bidirectional"))
      (node (ref "R28") (pin "P$2") (pinfunction "S_P$2") (pintype "passive"))
    )
    (net (code "9") (name "CV_NORMALIZATION") (class "Default")
      (node (ref "J7") (pin "P2") (pinfunction "2_P2") (pintype "passive"))
      (node (ref "R57") (pin "2") (pinfunction "2_2") (pintype "passive"))
    )
    (net (code "10") (name "DAMP_ATT") (class "Default")
      (node (ref "IC4") (pin "13") (pinfunction "X0_13") (pintype "bidirectional"))
      (node (ref "R47") (pin "P$2") (pinfunction "S_P$2") (pintype "passive"))
    )
    (net (code "11") (name "DAMP_CV") (class "Default")
      (node (ref "C28") (pin "2") (pinfunction "2_2") (pintype "passive"))
      (node (ref "IC2") (pin "21") (pinfunction "PA5/SPI1_SCK/ADC5/DAC2_21") (pintype "bidirectional"))
      (node (ref "IC7") (pin "14") (pinfunction "OUT_14") (pintype "output"))
      (node (ref "R25") (pin "1") (pinfunction "1_1") (pintype "passive"))
    )
    (net (code "12") (name "DAMP_POT") (class "Default")
      (node (ref "IC4") (pin "5") (pinfunction "X5_5") (pintype "bidirectional"))
      (node (ref "R29") (pin "P$2") (pinfunction "S_P$2") (pintype "passive"))
    )
    (net (code "13") (name "FM_CV") (class "Default")
      (node (ref "C29") (pin "2") (pinfunction "2_2") (pintype "passive"))
      (node (ref "IC2") (pin "20") (pinfunction "PA4/SPI1_NSS/SPI3_NSS/USART2_CK/I2S3_WS/ADC4/DAC1_20") (pintype "bidirectional"))
      (node (ref "IC7") (pin "8") (pinfunction "OUT_8") (pintype "output"))
      (node (ref "R26") (pin "1") (pinfunction "1_1") (pintype "passive"))
    )
    (net (code "14") (name "FREQUENCY_ATT") (class "Default")
      (node (ref "IC4") (pin "1") (pinfunction "X4_1") (pintype "bidirectional"))
      (node (ref "R46") (pin "P$2") (pinfunction "S_P$2") (pintype "passive"))
    )
    (net (code "15") (name "FREQUENCY_POT") (class "Default")
      (node (ref "IC2") (pin "11") (pinfunction "PC3/SPI2_MOSI/I2S2_SD/ADC13_11") (pintype "bidirectional"))
      (node (ref "R9") (pin "P$2") (pinfunction "S_P$2") (pintype "passive"))
    )
    (net (code "16") (name "GEOMETRY_ATT") (class "Default")
      (node (ref "IC4") (pin "14") (pinfunction "X1_14") (pintype "bidirectional"))
      (node (ref "R48") (pin "P$2") (pinfunction "S_P$2") (pintype "passive"))
    )
    (net (code "17") (name "GEOMETRY_CV") (class "Default")
      (node (ref "C36") (pin "2") (pinfunction "2_2") (pintype "passive"))
      (node (ref "IC2") (pin "22") (pinfunction "PA6/SPI1_MISO/ADC6/TIM3_CH1_22") (pintype "bidirectional"))
      (node (ref "IC7") (pin "1") (pinfunction "OUT_1") (pintype "output"))
      (node (ref "R31") (pin "1") (pinfunction "1_1") (pintype "passive"))
    )
    (net (code "18") (name "GEOMETRY_POT") (class "Default")
      (node (ref "IC2") (pin "10") (pinfunction "PC2/SPI2_MISO/ADC12_10") (pintype "bidirectional"))
      (node (ref "R10") (pin "P$2") (pinfunction "S_P$2") (pintype "passive"))
    )
    (net (code "19") (name "GND") (class "Default")
      (node (ref "C1") (pin "+") (pinfunction "+_+") (pintype "passive"))
      (node (ref "C10") (pin "2") (pinfunction "2_2") (pintype "passive"))
      (node (ref "C11") (pin "2") (pinfunction "2_2") (pintype "passive"))
      (node (ref "C12") (pin "-") (pinfunction "-_-") (pintype "passive"))
      (node (ref "C13") (pin "2") (pinfunction "2_2") (pintype "passive"))
      (node (ref "C15") (pin "2") (pinfunction "2_2") (pintype "passive"))
      (node (ref "C16") (pin "2") (pinfunction "2_2") (pintype "passive"))
      (node (ref "C17") (pin "2") (pinfunction "2_2") (pintype "passive"))
      (node (ref "C18") (pin "2") (pinfunction "2_2") (pintype "passive"))
      (node (ref "C19") (pin "2") (pinfunction "2_2") (pintype "passive"))
      (node (ref "C2") (pin "-") (pinfunction "-_-") (pintype "passive"))
      (node (ref "C20") (pin "2") (pinfunction "2_2") (pintype "passive"))
      (node (ref "C21") (pin "-") (pinfunction "-_-") (pintype "passive"))
      (node (ref "C22") (pin "2") (pinfunction "2_2") (pintype "passive"))
      (node (ref "C23") (pin "1") (pinfunction "1_1") (pintype "passive"))
      (node (ref "C24") (pin "1") (pinfunction "1_1") (pintype "passive"))
      (node (ref "C25") (pin "2") (pinfunction "2_2") (pintype "passive"))
      (node (ref "C27") (pin "2") (pinfunction "2_2") (pintype "passive"))
      (node (ref "C3") (pin "-") (pinfunction "-_-") (pintype "passive"))
      (node (ref "C30") (pin "2") (pinfunction "2_2") (pintype "passive"))
      (node (ref "C31") (pin "2") (pinfunction "2_2") (pintype "passive"))
      (node (ref "C34") (pin "-") (pinfunction "-_-") (pintype "passive"))
      (node (ref "C35") (pin "2") (pinfunction "2_2") (pintype "passive"))
      (node (ref "C37") (pin "2") (pinfunction "2_2") (pintype "passive"))
      (node (ref "C39") (pin "2") (pinfunction "2_2") (pintype "passive"))
      (node (ref "C4") (pin "1") (pinfunction "1_1") (pintype "passive"))
      (node (ref "C41") (pin "-") (pinfunction "-_-") (pintype "passive"))
      (node (ref "C44") (pin "2") (pinfunction "2_2") (pintype "passive"))
      (node (ref "C45") (pin "1") (pinfunction "1_1") (pintype "passive"))
      (node (ref "C46") (pin "-") (pinfunction "-_-") (pintype "passive"))
      (node (ref "C47") (pin "2") (pinfunction "2_2") (pintype "passive"))
      (node (ref "C48") (pin "2") (pinfunction "2_2") (pintype "passive"))
      (node (ref "C49") (pin "2") (pinfunction "2_2") (pintype "passive"))
      (node (ref "C5") (pin "1") (pinfunction "1_1") (pintype "passive"))
      (node (ref "C6") (pin "2") (pinfunction "2_2") (pintype "passive"))
      (node (ref "C7") (pin "2") (pinfunction "2_2") (pintype "passive"))
      (node (ref "C8") (pin "-") (pinfunction "-_-") (pintype "passive"))
      (node (ref "C9") (pin "2") (pinfunction "2_2") (pintype "passive"))
      (node (ref "D3") (pin "1") (pinfunction "A_1") (pintype "passive"))
      (node (ref "IC1") (pin "1") (pinfunction "GND_1") (pintype "power_in"))
      (node (ref "IC2") (pin "12") (pinfunction "VSSA_12") (pintype "power_in"))
      (node (ref "IC2") (pin "18") (pinfunction "VSS_4_18") (pintype "power_in"))
      (node (ref "IC2") (pin "26") (pinfunction "PB0/ADC8/TIM3_CH3_26") (pintype "bidirectional"))
      (node (ref "IC2") (pin "28") (pinfunction "PB2/BOOT1_28") (pintype "bidirectional"))
      (node (ref "IC2") (pin "63") (pinfunction "VSS_3_63") (pintype "power_in"))
      (node (ref "IC3") (pin "1") (pinfunction "C_1") (pintype "passive"))
      (node (ref "IC4") (pin "6") (pinfunction "INH_6") (pintype "input"))
      (node (ref "IC4") (pin "7") (pinfunction "VEE_7") (pintype "power_in"))
      (node (ref "IC4") (pin "8") (pinfunction "GND_8") (pintype "power_in"))
      (node (ref "IC5") (pin "3") (pinfunction "+IN_3") (pintype "input"))
      (node (ref "IC5") (pin "4") (pinfunction "V-_4") (pintype "power_in"))
      (node (ref "IC5") (pin "5") (pinfunction "+IN_5") (pintype "input"))
      (node (ref "IC6") (pin "11") (pinfunction "HPGND_11") (pintype "bidirectional"))
      (node (ref "IC6") (pin "15") (pinfunction "AGND_15") (pintype "bidirectional"))
      (node (ref "IC6") (pin "21") (pinfunction "MODE_21") (pintype "bidirectional"))
      (node (ref "IC6") (pin "22") (pinfunction "CSB_22") (pintype "bidirectional"))
      (node (ref "IC6") (pin "28") (pinfunction "DGND_28") (pintype "bidirectional"))
      (node (ref "IC7") (pin "10") (pinfunction "+IN_10") (pintype "input"))
      (node (ref "IC7") (pin "11") (pinfunction "V-_11") (pintype "power_in"))
      (node (ref "IC7") (pin "12") (pinfunction "+IN_12") (pintype "input"))
      (node (ref "IC7") (pin "3") (pinfunction "+IN_3") (pintype "input"))
      (node (ref "IC7") (pin "5") (pinfunction "+IN_5") (pintype "input"))
      (node (ref "IC8") (pin "3") (pinfunction "+IN_3") (pintype "input"))
      (node (ref "IC8") (pin "5") (pinfunction "+IN_5") (pintype "input"))
      (node (ref "J1") (pin "P1") (pinfunction "1_P1") (pintype "passive"))
      (node (ref "J10") (pin "P1") (pinfunction "1_P1") (pintype "passive"))
      (node (ref "J2") (pin "P1") (pinfunction "1_P1") (pintype "passive"))
      (node (ref "J3") (pin "P1") (pinfunction "1_P1") (pintype "passive"))
      (node (ref "J4") (pin "P1") (pinfunction "1_P1") (pintype "passive"))
      (node (ref "J5") (pin "P1") (pinfunction "1_P1") (pintype "passive"))
      (node (ref "J6") (pin "P1") (pinfunction "1_P1") (pintype "passive"))
      (node (ref "J7") (pin "P1") (pinfunction "1_P1") (pintype "passive"))
      (node (ref "J8") (pin "P1") (pinfunction "1_P1") (pintype "passive"))
      (node (ref "J9") (pin "P1") (pinfunction "1_P1") (pintype "passive"))
      (node (ref "JP1") (pin "3") (pinfunction "3_3") (pintype "passive"))
      (node (ref "JP1") (pin "5") (pinfunction "5_5") (pintype "passive"))
      (node (ref "JP1") (pin "9") (pinfunction "9_9") (pintype "passive"))
      (node (ref "JP2") (pin "1") (pinfunction "1_1") (pintype "passive"))
      (node (ref "JP3") (pin "3") (pinfunction "3_3") (pintype "passive"))
      (node (ref "JP3") (pin "4") (pinfunction "4_4") (pintype "passive"))
      (node (ref "JP3") (pin "5") (pinfunction "5_5") (pintype "passive"))
      (node (ref "JP3") (pin "6") (pinfunction "6_6") (pintype "passive"))
      (node (ref "JP3") (pin "7") (pinfunction "7_7") (pintype "passive"))
      (node (ref "JP3") (pin "8") (pinfunction "8_8") (pintype "passive"))
      (node (ref "LED1") (pin "2") (pinfunction "C_2") (pintype "bidirectional"))
      (node (ref "LED2") (pin "2") (pinfunction "C_2") (pintype "bidirectional"))
      (node (ref "Q2") (pin "E") (pinfunction "E_E") (pintype "passive"))
      (node (ref "R10") (pin "P$3") (pinfunction "A_P$3") (pintype "passive"))
      (node (ref "R27") (pin "2") (pinfunction "2_2") (pintype "passive"))
      (node (ref "R28") (pin "P$3") (pinfunction "A_P$3") (pintype "passive"))
      (node (ref "R29") (pin "P$3") (pinfunction "A_P$3") (pintype "passive"))
      (node (ref "R30") (pin "P$3") (pinfunction "A_P$3") (pintype "passive"))
      (node (ref "R33") (pin "1") (pinfunction "1_1") (pintype "passive"))
      (node (ref "R38") (pin "1") (pinfunction "1_1") (pintype "passive"))
      (node (ref "R45") (pin "P$3") (pinfunction "A_P$3") (pintype "passive"))
      (node (ref "R46") (pin "P$3") (pinfunction "A_P$3") (pintype "passive"))
      (node (ref "R47") (pin "P$3") (pinfunction "A_P$3") (pintype "passive"))
      (node (ref "R48") (pin "P$3") (pinfunction "A_P$3") (pintype "passive"))
      (node (ref "R49") (pin "P$3") (pinfunction "A_P$3") (pintype "passive"))
      (node (ref "R51") (pin "1") (pinfunction "1_1") (pintype "passive"))
      (node (ref "R7") (pin "1") (pinfunction "1_1") (pintype "passive"))
      (node (ref "R9") (pin "P$3") (pinfunction "A_P$3") (pintype "passive"))
      (node (ref "SW1") (pin "1") (pinfunction "1_1") (pintype "passive"))
      (node (ref "SW1") (pin "2") (pinfunction "2_2") (pintype "passive"))
      (node (ref "SW2") (pin "1") (pinfunction "1_1") (pintype "passive"))
      (node (ref "SW2") (pin "2") (pinfunction "2_2") (pintype "passive"))
      (node (ref "SW3") (pin "A") (pinfunction "P_A") (pintype "passive"))
      (node (ref "SW3") (pin "A'") (pinfunction "P1_A'") (pintype "passive"))
    )
    (net (code "20") (name "I2C_SCL") (class "Default")
      (node (ref "IC2") (pin "29") (pinfunction "PB10/SPI2_SCK/I2S_SCK/I2C2_SCL/USART3_TX_29") (pintype "bidirectional"))
      (node (ref "IC6") (pin "24") (pinfunction "SCLK_24") (pintype "bidirectional"))
      (node (ref "R16") (pin "1") (pinfunction "1_1") (pintype "passive"))
    )
    (net (code "21") (name "I2C_SDA") (class "Default")
      (node (ref "IC2") (pin "30") (pinfunction "PB11/I2C2_SDA/USART3_RX_30") (pintype "bidirectional"))
      (node (ref "IC6") (pin "23") (pinfunction "SDIN_23") (pintype "bidirectional"))
      (node (ref "R17") (pin "1") (pinfunction "1_1") (pintype "passive"))
    )
    (net (code "22") (name "I2S_LRCK") (class "Default")
      (node (ref "IC2") (pin "33") (pinfunction "PB12/SPI2_NSS/I2S2_WS/I2C2_SMBA/USART3_CK/TIM1_BKIN_33") (pintype "bidirectional"))
      (node (ref "IC6") (pin "5") (pinfunction "DACLRC_5") (pintype "bidirectional"))
      (node (ref "IC6") (pin "7") (pinfunction "ADCLRC_7") (pintype "bidirectional"))
    )
    (net (code "23") (name "I2S_SCK") (class "Default")
      (node (ref "IC2") (pin "34") (pinfunction "PB13/SPI2_SCK/I2S2_SCK/USART3_CTS/TIM1_CH1N_34") (pintype "bidirectional"))
      (node (ref "IC6") (pin "3") (pinfunction "BCLK_3") (pintype "bidirectional"))
    )
    (net (code "24") (name "I2S_SIN") (class "Default")
      (node (ref "IC2") (pin "35") (pinfunction "PB14/SPI2_MISO/USART3_RTS/TIM1_CH2N_35") (pintype "bidirectional"))
      (node (ref "IC6") (pin "6") (pinfunction "ADCDAT_6") (pintype "bidirectional"))
    )
    (net (code "25") (name "I2S_SOUT") (class "Default")
      (node (ref "IC2") (pin "36") (pinfunction "PB15/SPI2_MOSI/I2S2_SD/TIM1_CH3N_36") (pintype "bidirectional"))
      (node (ref "IC6") (pin "4") (pinfunction "DACDAT_4") (pintype "bidirectional"))
    )
    (net (code "26") (name "IN_1") (class "Default")
      (node (ref "IC6") (pin "20") (pinfunction "LLINEIN_20") (pintype "bidirectional"))
      (node (ref "R27") (pin "1") (pinfunction "1_1") (pintype "passive"))
    )
    (net (code "27") (name "IN_2") (class "Default")
      (node (ref "C40") (pin "+") (pinfunction "+_+") (pintype "passive"))
      (node (ref "IC6") (pin "19") (pinfunction "RLINEIN_19") (pintype "bidirectional"))
    )
    (net (code "28") (name "JTCK") (class "Default")
      (node (ref "IC2") (pin "49") (pinfunction "PA14/JTCK-SWCLK_49") (pintype "bidirectional"))
      (node (ref "JP1") (pin "4") (pinfunction "4_4") (pintype "passive"))
    )
    (net (code "29") (name "JTDI") (class "Default")
      (node (ref "IC2") (pin "50") (pinfunction "PA15/JTDI/SPI3_NSS/I2S3_WS_50") (pintype "bidirectional"))
      (node (ref "JP1") (pin "8") (pinfunction "8_8") (pintype "passive"))
    )
    (net (code "30") (name "JTDO") (class "Default")
      (node (ref "IC2") (pin "55") (pinfunction "PB3/JTDO/SPI3_SCK/I2S3_SCK_55") (pintype "bidirectional"))
      (node (ref "JP1") (pin "6") (pinfunction "6_6") (pintype "passive"))
    )
    (net (code "31") (name "JTMS") (class "Default")
      (node (ref "IC2") (pin "46") (pinfunction "PA13/JTMS-SWDAT_46") (pintype "bidirectional"))
      (node (ref "JP1") (pin "2") (pinfunction "2_2") (pintype "passive"))
    )
    (net (code "32") (name "MAIN_OUT") (class "Default")
      (node (ref "C32") (pin "+") (pinfunction "+_+") (pintype "passive"))
      (node (ref "IC6") (pin "12") (pinfunction "LOUT_12") (pintype "bidirectional"))
    )
    (net (code "33") (name "MUXED_POTS") (class "Default")
      (node (ref "IC2") (pin "9") (pinfunction "PC1/ADC11_9") (pintype "bidirectional"))
      (node (ref "IC4") (pin "3") (pinfunction "X_3") (pintype "bidirectional"))
    )
    (net (code "34") (name "MUX_ADDR_0") (class "Default")
      (node (ref "IC2") (pin "59") (pinfunction "PB7/I2C1_SDA/TIM4_CH2/USART1_RX_59") (pintype "bidirectional"))
      (node (ref "IC4") (pin "11") (pinfunction "A_11") (pintype "input"))
    )
    (net (code "35") (name "MUX_ADDR_1") (class "Default")
      (node (ref "IC2") (pin "58") (pinfunction "PB6/I2C1_SCL/TIM4_CH1/USART1_TX_58") (pintype "bidirectional"))
      (node (ref "IC4") (pin "10") (pinfunction "B_10") (pintype "input"))
    )
    (net (code "36") (name "MUX_ADDR_2") (class "Default")
      (node (ref "IC2") (pin "57") (pinfunction "PB5/I2C1_SMBA/SPI1_MOSI/SPI3_MOSI/I2S3_SD_57") (pintype "bidirectional"))
      (node (ref "IC4") (pin "9") (pinfunction "C_9") (pintype "input"))
    )
    (net (code "37") (name "NORMALIZATION_PROBE") (class "Default")
      (node (ref "D3") (pin "3") (pinfunction "AC_3") (pintype "passive"))
      (node (ref "IC2") (pin "39") (pinfunction "PC8_39") (pintype "bidirectional"))
      (node (ref "R52") (pin "1") (pinfunction "1_1") (pintype "passive"))
      (node (ref "R53") (pin "1") (pinfunction "1_1") (pintype "passive"))
      (node (ref "R57") (pin "1") (pinfunction "1_1") (pintype "passive"))
    )
    (net (code "38") (name "Net-(C32-Pad-)") (class "Default")
      (node (ref "C32") (pin "-") (pinfunction "-_-") (pintype "passive"))
      (node (ref "R33") (pin "2") (pinfunction "2_2") (pintype "passive"))
      (node (ref "R40") (pin "2") (pinfunction "2_2") (pintype "passive"))
    )
    (net (code "39") (name "Net-(C33-Pad-)") (class "Default")
      (node (ref "C33") (pin "-") (pinfunction "-_-") (pintype "passive"))
      (node (ref "R38") (pin "2") (pinfunction "2_2") (pintype "passive"))
      (node (ref "R43") (pin "2") (pinfunction "2_2") (pintype "passive"))
    )
    (net (code "40") (name "Net-(C40-Pad-)") (class "Default")
      (node (ref "C40") (pin "-") (pinfunction "-_-") (pintype "passive"))
      (node (ref "C49") (pin "1") (pinfunction "1_1") (pintype "passive"))
      (node (ref "R51") (pin "2") (pinfunction "2_2") (pintype "passive"))
      (node (ref "R54") (pin "1") (pinfunction "1_1") (pintype "passive"))
    )
    (net (code "41") (name "Net-(D1-PadA)") (class "Default")
      (node (ref "D1") (pin "A") (pinfunction "A_A") (pintype "passive"))
      (node (ref "L1") (pin "1") (pinfunction "1_1") (pintype "passive"))
    )
    (net (code "42") (name "Net-(D2-PadC)") (class "Default")
      (node (ref "D2") (pin "C") (pinfunction "C_C") (pintype "passive"))
      (node (ref "L2") (pin "1") (pinfunction "1_1") (pintype "passive"))
    )
    (net (code "43") (name "Net-(IC1-VIN)") (class "Default")
      (node (ref "C2") (pin "+") (pinfunction "+_+") (pintype "passive"))
      (node (ref "IC1") (pin "2") (pinfunction "VIN_2") (pintype "input"))
      (node (ref "R2") (pin "1") (pinfunction "1_1") (pintype "passive"))
    )
    (net (code "44") (name "Net-(IC2-PC0{slash}ADC10)") (class "Default")
      (node (ref "IC2") (pin "8") (pinfunction "PC0/ADC10_8") (pintype "bidirectional"))
      (node (ref "R4") (pin "1") (pinfunction "1_1") (pintype "passive"))
    )
    (net (code "45") (name "Net-(IC2-PC10{slash}SPI3_SCK{slash}I2S3_SCK{slash}UART4_TX)") (class "Default")
      (node (ref "IC2") (pin "51") (pinfunction "PC10/SPI3_SCK/I2S3_SCK/UART4_TX_51") (pintype "bidirectional"))
      (node (ref "R5") (pin "1") (pinfunction "1_1") (pintype "passive"))
    )
    (net (code "46") (name "Net-(IC2-PC11{slash}UART4_RX{slash}SPI3_MISO{slash}USART3_RX)") (class "Default")
      (node (ref "IC2") (pin "52") (pinfunction "PC11/UART4_RX/SPI3_MISO/USART3_RX_52") (pintype "bidirectional"))
      (node (ref "R3") (pin "1") (pinfunction "1_1") (pintype "passive"))
    )
    (net (code "47") (name "Net-(IC2-PC12{slash}UART5_TX{slash}I2S3_SD{slash}USART3_CK)") (class "Default")
      (node (ref "IC2") (pin "53") (pinfunction "PC12/UART5_TX/I2S3_SD/USART3_CK_53") (pintype "bidirectional"))
      (node (ref "R1") (pin "1") (pinfunction "1_1") (pintype "passive"))
    )
    (net (code "48") (name "Net-(IC2-PD0{slash}OSC_IN)") (class "Default")
      (node (ref "C5") (pin "2") (pinfunction "2_2") (pintype "passive"))
      (node (ref "IC2") (pin "5") (pinfunction "PD0/OSC_IN_5") (pintype "bidirectional"))
      (node (ref "Q1") (pin "2") (pinfunction "2_2") (pintype "passive"))
    )
    (net (code "49") (name "Net-(IC2-PD1{slash}OSC_OUT)") (class "Default")
      (node (ref "C4") (pin "2") (pinfunction "2_2") (pintype "passive"))
      (node (ref "IC2") (pin "6") (pinfunction "PD1/OSC_OUT_6") (pintype "bidirectional"))
      (node (ref "Q1") (pin "1") (pinfunction "1_1") (pintype "passive"))
    )
    (net (code "50") (name "Net-(IC2-VCAP_1)") (class "Default")
      (node (ref "C16") (pin "1") (pinfunction "1_1") (pintype "passive"))
      (node (ref "IC2") (pin "31") (pinfunction "VCAP_1_31") (pintype "power_in"))
    )
    (net (code "51") (name "Net-(IC2-VCAP_2)") (class "Default")
      (node (ref "C22") (pin "1") (pinfunction "1_1") (pintype "passive"))
      (node (ref "IC2") (pin "47") (pinfunction "VCAP_2_47") (pintype "power_in"))
    )
    (net (code "52") (name "Net-(IC5A--IN)") (class "Default")
      (node (ref "C26") (pin "1") (pinfunction "1_1") (pintype "passive"))
      (node (ref "IC5") (pin "2") (pinfunction "-IN_2") (pintype "input"))
      (node (ref "R18") (pin "2") (pinfunction "2_2") (pintype "passive"))
      (node (ref "R19") (pin "1") (pinfunction "1_1") (pintype "passive"))
      (node (ref "R20") (pin "1") (pinfunction "1_1") (pintype "passive"))
    )
    (net (code "53") (name "Net-(IC5B--IN)") (class "Default")
      (node (ref "C14") (pin "1") (pinfunction "1_1") (pintype "passive"))
      (node (ref "IC5") (pin "6") (pinfunction "-IN_6") (pintype "input"))
      (node (ref "R13") (pin "2") (pinfunction "2_2") (pintype "passive"))
      (node (ref "R14") (pin "1") (pinfunction "1_1") (pintype "passive"))
      (node (ref "R15") (pin "1") (pinfunction "1_1") (pintype "passive"))
    )
    (net (code "54") (name "Net-(IC6-VMID)") (class "Default")
      (node (ref "C34") (pin "+") (pinfunction "+_+") (pintype "passive"))
      (node (ref "C35") (pin "1") (pinfunction "1_1") (pintype "passive"))
      (node (ref "IC6") (pin "16") (pinfunction "VMID_16") (pintype "bidirectional"))
    )
    (net (code "55") (name "Net-(IC6-XTI{slash}MCLK)") (class "Default")
      (node (ref "C24") (pin "2") (pinfunction "2_2") (pintype "passive"))
      (node (ref "IC6") (pin "25") (pinfunction "XTI/MCLK_25") (pintype "bidirectional"))
      (node (ref "Q3") (pin "2") (pinfunction "2_2") (pintype "passive"))
    )
    (net (code "56") (name "Net-(IC6-XTO)") (class "Default")
      (node (ref "C23") (pin "2") (pinfunction "2_2") (pintype "passive"))
      (node (ref "IC6") (pin "26") (pinfunction "XTO_26") (pintype "bidirectional"))
      (node (ref "Q3") (pin "1") (pinfunction "1_1") (pintype "passive"))
    )
    (net (code "57") (name "Net-(IC7A--IN)") (class "Default")
      (node (ref "C36") (pin "1") (pinfunction "1_1") (pintype "passive"))
      (node (ref "IC7") (pin "2") (pinfunction "-IN_2") (pintype "input"))
      (node (ref "R31") (pin "2") (pinfunction "2_2") (pintype "passive"))
      (node (ref "R34") (pin "1") (pinfunction "1_1") (pintype "passive"))
      (node (ref "R36") (pin "1") (pinfunction "1_1") (pintype "passive"))
    )
    (net (code "58") (name "Net-(IC7B--IN)") (class "Default")
      (node (ref "C38") (pin "1") (pinfunction "1_1") (pintype "passive"))
      (node (ref "IC7") (pin "6") (pinfunction "-IN_6") (pintype "input"))
      (node (ref "R32") (pin "2") (pinfunction "2_2") (pintype "passive"))
      (node (ref "R35") (pin "1") (pinfunction "1_1") (pintype "passive"))
      (node (ref "R37") (pin "1") (pinfunction "1_1") (pintype "passive"))
    )
    (net (code "59") (name "Net-(IC7C--IN)") (class "Default")
      (node (ref "C29") (pin "1") (pinfunction "1_1") (pintype "passive"))
      (node (ref "IC7") (pin "9") (pinfunction "-IN_9") (pintype "input"))
      (node (ref "R22") (pin "1") (pinfunction "1_1") (pintype "passive"))
      (node (ref "R24") (pin "1") (pinfunction "1_1") (pintype "passive"))
      (node (ref "R26") (pin "2") (pinfunction "2_2") (pintype "passive"))
    )
    (net (code "60") (name "Net-(IC7D--IN)") (class "Default")
      (node (ref "C28") (pin "1") (pinfunction "1_1") (pintype "passive"))
      (node (ref "IC7") (pin "13") (pinfunction "-IN_13") (pintype "input"))
      (node (ref "R21") (pin "1") (pinfunction "1_1") (pintype "passive"))
      (node (ref "R23") (pin "1") (pinfunction "1_1") (pintype "passive"))
      (node (ref "R25") (pin "2") (pinfunction "2_2") (pintype "passive"))
    )
    (net (code "61") (name "Net-(IC8A--IN)") (class "Default")
      (node (ref "C42") (pin "1") (pinfunction "1_1") (pintype "passive"))
      (node (ref "IC8") (pin "2") (pinfunction "-IN_2") (pintype "input"))
      (node (ref "R39") (pin "1") (pinfunction "1_1") (pintype "passive"))
      (node (ref "R40") (pin "1") (pinfunction "1_1") (pintype "passive"))
      (node (ref "R41") (pin "2") (pinfunction "2_2") (pintype "passive"))
    )
    (net (code "62") (name "Net-(IC8A-OUT)") (class "Default")
      (node (ref "C42") (pin "2") (pinfunction "2_2") (pintype "passive"))
      (node (ref "IC8") (pin "1") (pinfunction "OUT_1") (pintype "output"))
      (node (ref "R41") (pin "1") (pinfunction "1_1") (pintype "passive"))
      (node (ref "R55") (pin "2") (pinfunction "2_2") (pintype "passive"))
    )
    (net (code "63") (name "Net-(IC8B--IN)") (class "Default")
      (node (ref "C43") (pin "1") (pinfunction "1_1") (pintype "passive"))
      (node (ref "IC8") (pin "6") (pinfunction "-IN_6") (pintype "input"))
      (node (ref "R42") (pin "2") (pinfunction "2_2") (pintype "passive"))
      (node (ref "R43") (pin "1") (pinfunction "1_1") (pintype "passive"))
      (node (ref "R44") (pin "1") (pinfunction "1_1") (pintype "passive"))
    )
    (net (code "64") (name "Net-(IC8B-OUT)") (class "Default")
      (node (ref "C43") (pin "2") (pinfunction "2_2") (pintype "passive"))
      (node (ref "IC8") (pin "7") (pinfunction "OUT_7") (pintype "output"))
      (node (ref "R42") (pin "1") (pinfunction "1_1") (pintype "passive"))
      (node (ref "R56") (pin "2") (pinfunction "2_2") (pintype "passive"))
    )
    (net (code "65") (name "Net-(J1-3)") (class "Default")
      (node (ref "J1") (pin "P3") (pinfunction "3_P3") (pintype "passive"))
      (node (ref "R19") (pin "2") (pinfunction "2_2") (pintype "passive"))
    )
    (net (code "66") (name "Net-(J2-2)") (class "Default")
      (node (ref "J2") (pin "P2") (pinfunction "2_P2") (pintype "passive"))
      (node (ref "R50") (pin "1") (pinfunction "1_1") (pintype "passive"))
    )
    (net (code "67") (name "Net-(J2-3)") (class "Default")
      (node (ref "J2") (pin "P3") (pinfunction "3_P3") (pintype "passive"))
      (node (ref "R22") (pin "2") (pinfunction "2_2") (pintype "passive"))
    )
    (net (code "68") (name "Net-(J3-3)") (class "Default")
      (node (ref "J3") (pin "P3") (pinfunction "3_P3") (pintype "passive"))
      (node (ref "R21") (pin "2") (pinfunction "2_2") (pintype "passive"))
    )
    (net (code "69") (name "Net-(J4-3)") (class "Default")
      (node (ref "J4") (pin "P3") (pinfunction "3_P3") (pintype "passive"))
      (node (ref "R34") (pin "2") (pinfunction "2_2") (pintype "passive"))
    )
    (net (code "70") (name "Net-(J5-3)") (class "Default")
      (node (ref "J5") (pin "P3") (pinfunction "3_P3") (pintype "passive"))
      (node (ref "R35") (pin "2") (pinfunction "2_2") (pintype "passive"))
    )
    (net (code "71") (name "Net-(J6-2)") (class "Default")
      (node (ref "J6") (pin "P2") (pinfunction "2_P2") (pintype "passive"))
      (node (ref "R52") (pin "2") (pinfunction "2_2") (pintype "passive"))
    )
    (net (code "72") (name "Net-(J6-3)") (class "Default")
      (node (ref "J6") (pin "P3") (pinfunction "3_P3") (pintype "passive"))
      (node (ref "R11") (pin "1") (pinfunction "1_1") (pintype "passive"))
    )
    (net (code "73") (name "Net-(J7-3)") (class "Default")
      (node (ref "J7") (pin "P3") (pinfunction "3_P3") (pintype "passive"))
      (node (ref "R14") (pin "2") (pinfunction "2_2") (pintype "passive"))
    )
    (net (code "74") (name "Net-(J8-2)") (class "Default")
      (node (ref "J8") (pin "P2") (pinfunction "2_P2") (pintype "passive"))
      (node (ref "R53") (pin "2") (pinfunction "2_2") (pintype "passive"))
    )
    (net (code "75") (name "Net-(J8-3)") (class "Default")
      (node (ref "J8") (pin "P3") (pinfunction "3_P3") (pintype "passive"))
      (node (ref "R54") (pin "2") (pinfunction "2_2") (pintype "passive"))
    )
    (net (code "76") (name "Net-(J9-2)") (class "Default")
      (node (ref "J9") (pin "P2") (pinfunction "2_P2") (pintype "passive"))
      (node (ref "SJ1") (pin "2") (pinfunction "2_2") (pintype "passive"))
    )
    (net (code "77") (name "Net-(J9-3)") (class "Default")
      (node (ref "J9") (pin "P3") (pinfunction "3_P3") (pintype "passive"))
      (node (ref "R55") (pin "1") (pinfunction "1_1") (pintype "passive"))
    )
    (net (code "78") (name "Net-(J10-2)") (class "Default")
      (node (ref "J10") (pin "P2") (pinfunction "2_P2") (pintype "passive"))
      (node (ref "R39") (pin "2") (pinfunction "2_2") (pintype "passive"))
    )
    (net (code "79") (name "Net-(J10-3)") (class "Default")
      (node (ref "J10") (pin "P3") (pinfunction "3_P3") (pintype "passive"))
      (node (ref "R56") (pin "1") (pinfunction "1_1") (pintype "passive"))
    )
    (net (code "80") (name "Net-(JP3-Pad1)") (class "Default")
      (node (ref "JP3") (pin "1") (pinfunction "1_1") (pintype "passive"))
      (node (ref "JP3") (pin "2") (pinfunction "2_2") (pintype "passive"))
      (node (ref "L1") (pin "2") (pinfunction "2_2") (pintype "passive"))
    )
    (net (code "81") (name "Net-(JP3-Pad10)") (class "Default")
      (node (ref "JP3") (pin "10") (pinfunction "10_10") (pintype "passive"))
      (node (ref "JP3") (pin "9") (pinfunction "9_9") (pintype "passive"))
      (node (ref "L2") (pin "2") (pinfunction "2_2") (pintype "passive"))
    )
    (net (code "82") (name "Net-(LED1-GRN)") (class "Default")
      (node (ref "LED1") (pin "1") (pinfunction "GRN_1") (pintype "bidirectional"))
      (node (ref "R3") (pin "2") (pinfunction "2_2") (pintype "passive"))
    )
    (net (code "83") (name "Net-(LED1-RED)") (class "Default")
      (node (ref "LED1") (pin "3") (pinfunction "RED_3") (pintype "bidirectional"))
      (node (ref "R1") (pin "2") (pinfunction "2_2") (pintype "passive"))
    )
    (net (code "84") (name "Net-(LED2-GRN)") (class "Default")
      (node (ref "LED2") (pin "1") (pinfunction "GRN_1") (pintype "bidirectional"))
      (node (ref "R5") (pin "2") (pinfunction "2_2") (pintype "passive"))
    )
    (net (code "85") (name "Net-(LED2-RED)") (class "Default")
      (node (ref "LED2") (pin "3") (pinfunction "RED_3") (pintype "bidirectional"))
      (node (ref "R4") (pin "2") (pinfunction "2_2") (pintype "passive"))
    )
    (net (code "86") (name "Net-(Q2-PadB)") (class "Default")
      (node (ref "Q2") (pin "B") (pinfunction "B_B") (pintype "passive"))
      (node (ref "R11") (pin "2") (pinfunction "2_2") (pintype "passive"))
    )
    (net (code "87") (name "Net-(R44-Pad2)") (class "Default")
      (node (ref "R44") (pin "2") (pinfunction "2_2") (pintype "passive"))
      (node (ref "SJ1") (pin "1") (pinfunction "1_1") (pintype "passive"))
    )
    (net (code "88") (name "POSITION_ATT") (class "Default")
      (node (ref "IC4") (pin "15") (pinfunction "X2_15") (pintype "bidirectional"))
      (node (ref "R49") (pin "P$2") (pinfunction "S_P$2") (pintype "passive"))
    )
    (net (code "89") (name "POSITION_CV") (class "Default")
      (node (ref "C38") (pin "2") (pinfunction "2_2") (pintype "passive"))
      (node (ref "IC2") (pin "23") (pinfunction "PA7/SPI1_MOSI/ADC7/TIM3_CH2_23") (pintype "bidirectional"))
      (node (ref "IC7") (pin "7") (pinfunction "OUT_7") (pintype "output"))
      (node (ref "R32") (pin "1") (pinfunction "1_1") (pintype "passive"))
    )
    (net (code "90") (name "POSITION_POT") (class "Default")
      (node (ref "IC4") (pin "12") (pinfunction "X3_12") (pintype "bidirectional"))
      (node (ref "R30") (pin "P$2") (pinfunction "S_P$2") (pintype "passive"))
    )
    (net (code "91") (name "RESET") (class "Default")
      (node (ref "IC2") (pin "7") (pinfunction "NRST_7") (pintype "bidirectional"))
      (node (ref "JP1") (pin "10") (pinfunction "10_10") (pintype "passive"))
      (node (ref "R6") (pin "1") (pinfunction "1_1") (pintype "passive"))
      (node (ref "SW3") (pin "B") (pinfunction "S_B") (pintype "passive"))
      (node (ref "SW3") (pin "B'") (pinfunction "S1_B'") (pintype "passive"))
    )
    (net (code "92") (name "RX") (class "Default")
      (node (ref "IC2") (pin "43") (pinfunction "PA10/USART1_RX/TIM1_CH3_43") (pintype "bidirectional"))
      (node (ref "JP2") (pin "4") (pinfunction "4_4") (pintype "passive"))
    )
    (net (code "93") (name "STRUM") (class "Default")
      (node (ref "IC2") (pin "16") (pinfunction "PA2/USART2_TX/ADC2/TIM2_CH3_16") (pintype "bidirectional"))
      (node (ref "Q2") (pin "C") (pinfunction "C_C") (pintype "passive"))
      (node (ref "R8") (pin "1") (pinfunction "1_1") (pintype "passive"))
    )
    (net (code "94") (name "SW_MODE") (class "Default")
      (node (ref "IC2") (pin "61") (pinfunction "PB8/TIM4_CH3/I2C1_SCL_61") (pintype "bidirectional"))
      (node (ref "SW2") (pin "3") (pinfunction "3_3") (pintype "passive"))
      (node (ref "SW2") (pin "4") (pinfunction "4_4") (pintype "passive"))
    )
    (net (code "95") (name "SW_POLYPHONY") (class "Default")
      (node (ref "IC2") (pin "62") (pinfunction "PB9/SPI2_NSS/I2S2_WS/I2C1_SDA/TIM4_CH4_62") (pintype "bidirectional"))
      (node (ref "SW1") (pin "3") (pinfunction "3_3") (pintype "passive"))
      (node (ref "SW1") (pin "4") (pinfunction "4_4") (pintype "passive"))
    )
    (net (code "96") (name "TX") (class "Default")
      (node (ref "IC2") (pin "42") (pinfunction "PA9/USART1_TX/TIM1_CH2_42") (pintype "bidirectional"))
      (node (ref "JP2") (pin "5") (pinfunction "5_5") (pintype "passive"))
    )
    (net (code "97") (name "VBAT") (class "Default")
      (node (ref "IC2") (pin "1") (pinfunction "VBAT_1") (pintype "power_in"))
    )
    (net (code "98") (name "VCC") (class "Default")
      (node (ref "C3") (pin "+") (pinfunction "+_+") (pintype "passive"))
      (node (ref "C39") (pin "1") (pinfunction "1_1") (pintype "passive"))
      (node (ref "D1") (pin "C") (pinfunction "C_C") (pintype "passive"))
      (node (ref "IC8") (pin "8") (pinfunction "V+_8") (pintype "power_in"))
      (node (ref "R2") (pin "2") (pinfunction "2_2") (pintype "passive"))
    )
    (net (code "99") (name "VEE") (class "Default")
      (node (ref "C1") (pin "-") (pinfunction "-_-") (pintype "passive"))
      (node (ref "C45") (pin "2") (pinfunction "2_2") (pintype "passive"))
      (node (ref "D2") (pin "A") (pinfunction "A_A") (pintype "passive"))
      (node (ref "IC8") (pin "4") (pinfunction "V-_4") (pintype "power_in"))
      (node (ref "R12") (pin "1") (pinfunction "1_1") (pintype "passive"))
    )
    (net (code "100") (name "V_OCT_CV") (class "Default")
      (node (ref "C14") (pin "2") (pinfunction "2_2") (pintype "passive"))
      (node (ref "IC2") (pin "15") (pinfunction "PA1/USART2_RTS/UART4_RX/ADC1/TIM2_CH2_15") (pintype "bidirectional"))
      (node (ref "IC5") (pin "7") (pinfunction "OUT_7") (pintype "output"))
      (node (ref "R13") (pin "1") (pinfunction "1_1") (pintype "passive"))
    )
    (net (code "101") (name "unconnected-(IC2-PA3{slash}USART2_RX{slash}ADC3{slash}TIM2_CH4-Pad17)") (class "Default")
      (node (ref "IC2") (pin "17") (pinfunction "PA3/USART2_RX/ADC3/TIM2_CH4_17") (pintype "bidirectional"))
    )
    (net (code "102") (name "unconnected-(IC2-PA8{slash}USART1_CK{slash}TIM1_CH1{slash}MCO-Pad41)") (class "Default")
      (node (ref "IC2") (pin "41") (pinfunction "PA8/USART1_CK/TIM1_CH1/MCO_41") (pintype "bidirectional"))
    )
    (net (code "103") (name "unconnected-(IC2-PA11{slash}USART1_CTS{slash}CANRX{slash}USBDM{slash}TIM1_CH4-Pad44)") (class "Default")
      (node (ref "IC2") (pin "44") (pinfunction "PA11/USART1_CTS/CANRX/USBDM/TIM1_CH4_44") (pintype "bidirectional"))
    )
    (net (code "104") (name "unconnected-(IC2-PA12{slash}USART1_RTS{slash}CANTX{slash}USBDP{slash}TIM1_ETR-Pad45)") (class "Default")
      (node (ref "IC2") (pin "45") (pinfunction "PA12/USART1_RTS/CANTX/USBDP/TIM1_ETR_45") (pintype "bidirectional"))
    )
    (net (code "105") (name "unconnected-(IC2-PB1{slash}ADC9{slash}TIM3_CH4-Pad27)") (class "Default")
      (node (ref "IC2") (pin "27") (pinfunction "PB1/ADC9/TIM3_CH4_27") (pintype "bidirectional"))
    )
    (net (code "106") (name "unconnected-(IC2-PB4{slash}NJTRST{slash}SPI3_MISO{slash}SPI1_MISO-Pad56)") (class "Default")
      (node (ref "IC2") (pin "56") (pinfunction "PB4/NJTRST/SPI3_MISO/SPI1_MISO_56") (pintype "bidirectional"))
    )
    (net (code "107") (name "unconnected-(IC2-PC4{slash}ADC14-Pad24)") (class "Default")
      (node (ref "IC2") (pin "24") (pinfunction "PC4/ADC14_24") (pintype "bidirectional"))
    )
    (net (code "108") (name "unconnected-(IC2-PC5{slash}ADC15-Pad25)") (class "Default")
      (node (ref "IC2") (pin "25") (pinfunction "PC5/ADC15_25") (pintype "bidirectional"))
    )
    (net (code "109") (name "unconnected-(IC2-PC6{slash}I2S2_MCK-Pad37)") (class "Default")
      (node (ref "IC2") (pin "37") (pinfunction "PC6/I2S2_MCK_37") (pintype "bidirectional"))
    )
    (net (code "110") (name "unconnected-(IC2-PC7{slash}I2S3_MCK-Pad38)") (class "Default")
      (node (ref "IC2") (pin "38") (pinfunction "PC7/I2S3_MCK_38") (pintype "bidirectional"))
    )
    (net (code "111") (name "unconnected-(IC2-PC9{slash}I2S2_CKIN{slash}I2S3_CKIN-Pad40)") (class "Default")
      (node (ref "IC2") (pin "40") (pinfunction "PC9/I2S2_CKIN/I2S3_CKIN_40") (pintype "bidirectional"))
    )
    (net (code "112") (name "unconnected-(IC2-PC13-TAMPER-RTC-Pad2)") (class "Default")
      (node (ref "IC2") (pin "2") (pinfunction "PC13-TAMPER-RTC_2") (pintype "bidirectional"))
    )
    (net (code "113") (name "unconnected-(IC2-PC14{slash}OSC32_IN-Pad3)") (class "Default")
      (node (ref "IC2") (pin "3") (pinfunction "PC14/OSC32_IN_3") (pintype "bidirectional"))
    )
    (net (code "114") (name "unconnected-(IC2-PC15{slash}OSC_OUT-Pad4)") (class "Default")
      (node (ref "IC2") (pin "4") (pinfunction "PC15/OSC_OUT_4") (pintype "bidirectional"))
    )
    (net (code "115") (name "unconnected-(IC2-PD2{slash}TIM3-ETR-Pad54)") (class "Default")
      (node (ref "IC2") (pin "54") (pinfunction "PD2/TIM3-ETR_54") (pintype "bidirectional"))
    )
    (net (code "116") (name "unconnected-(IC6-CLKOUT-Pad2)") (class "Default")
      (node (ref "IC6") (pin "2") (pinfunction "CLKOUT_2") (pintype "bidirectional"))
    )
    (net (code "117") (name "unconnected-(IC6-LHPOUT-Pad9)") (class "Default")
      (node (ref "IC6") (pin "9") (pinfunction "LHPOUT_9") (pintype "bidirectional"))
    )
    (net (code "118") (name "unconnected-(IC6-MICBIAS-Pad17)") (class "Default")
      (node (ref "IC6") (pin "17") (pinfunction "MICBIAS_17") (pintype "bidirectional"))
    )
    (net (code "119") (name "unconnected-(IC6-MICIN-Pad18)") (class "Default")
      (node (ref "IC6") (pin "18") (pinfunction "MICIN_18") (pintype "bidirectional"))
    )
    (net (code "120") (name "unconnected-(IC6-RHPOUT-Pad10)") (class "Default")
      (node (ref "IC6") (pin "10") (pinfunction "RHPOUT_10") (pintype "bidirectional"))
    )
    (net (code "121") (name "unconnected-(J1-2-PadP2)") (class "Default")
      (node (ref "J1") (pin "P2") (pinfunction "2_P2") (pintype "passive"))
    )
    (net (code "122") (name "unconnected-(J3-2-PadP2)") (class "Default")
      (node (ref "J3") (pin "P2") (pinfunction "2_P2") (pintype "passive"))
    )
    (net (code "123") (name "unconnected-(J4-2-PadP2)") (class "Default")
      (node (ref "J4") (pin "P2") (pinfunction "2_P2") (pintype "passive"))
    )
    (net (code "124") (name "unconnected-(J5-2-PadP2)") (class "Default")
      (node (ref "J5") (pin "P2") (pinfunction "2_P2") (pintype "passive"))
    )
    (net (code "125") (name "unconnected-(JP1-Pad7)") (class "Default")
      (node (ref "JP1") (pin "7") (pinfunction "7_7") (pintype "passive"))
    )
    (net (code "126") (name "unconnected-(JP2-Pad2)") (class "Default")
      (node (ref "JP2") (pin "2") (pinfunction "2_2") (pintype "passive"))
    )
    (net (code "127") (name "unconnected-(JP2-Pad3)") (class "Default")
      (node (ref "JP2") (pin "3") (pinfunction "3_3") (pintype "passive"))
    )
    (net (code "128") (name "unconnected-(JP2-Pad6)") (class "Default")
      (node (ref "JP2") (pin "6") (pinfunction "6_6") (pintype "passive"))
    )
  )
)
